# output_stage.net
KiCad netlist of a schematic drawn in EAGLE
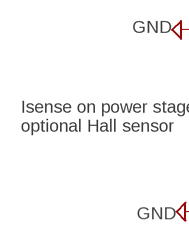
[diagram p0: schematic, sheet 1, part 1 of 2]
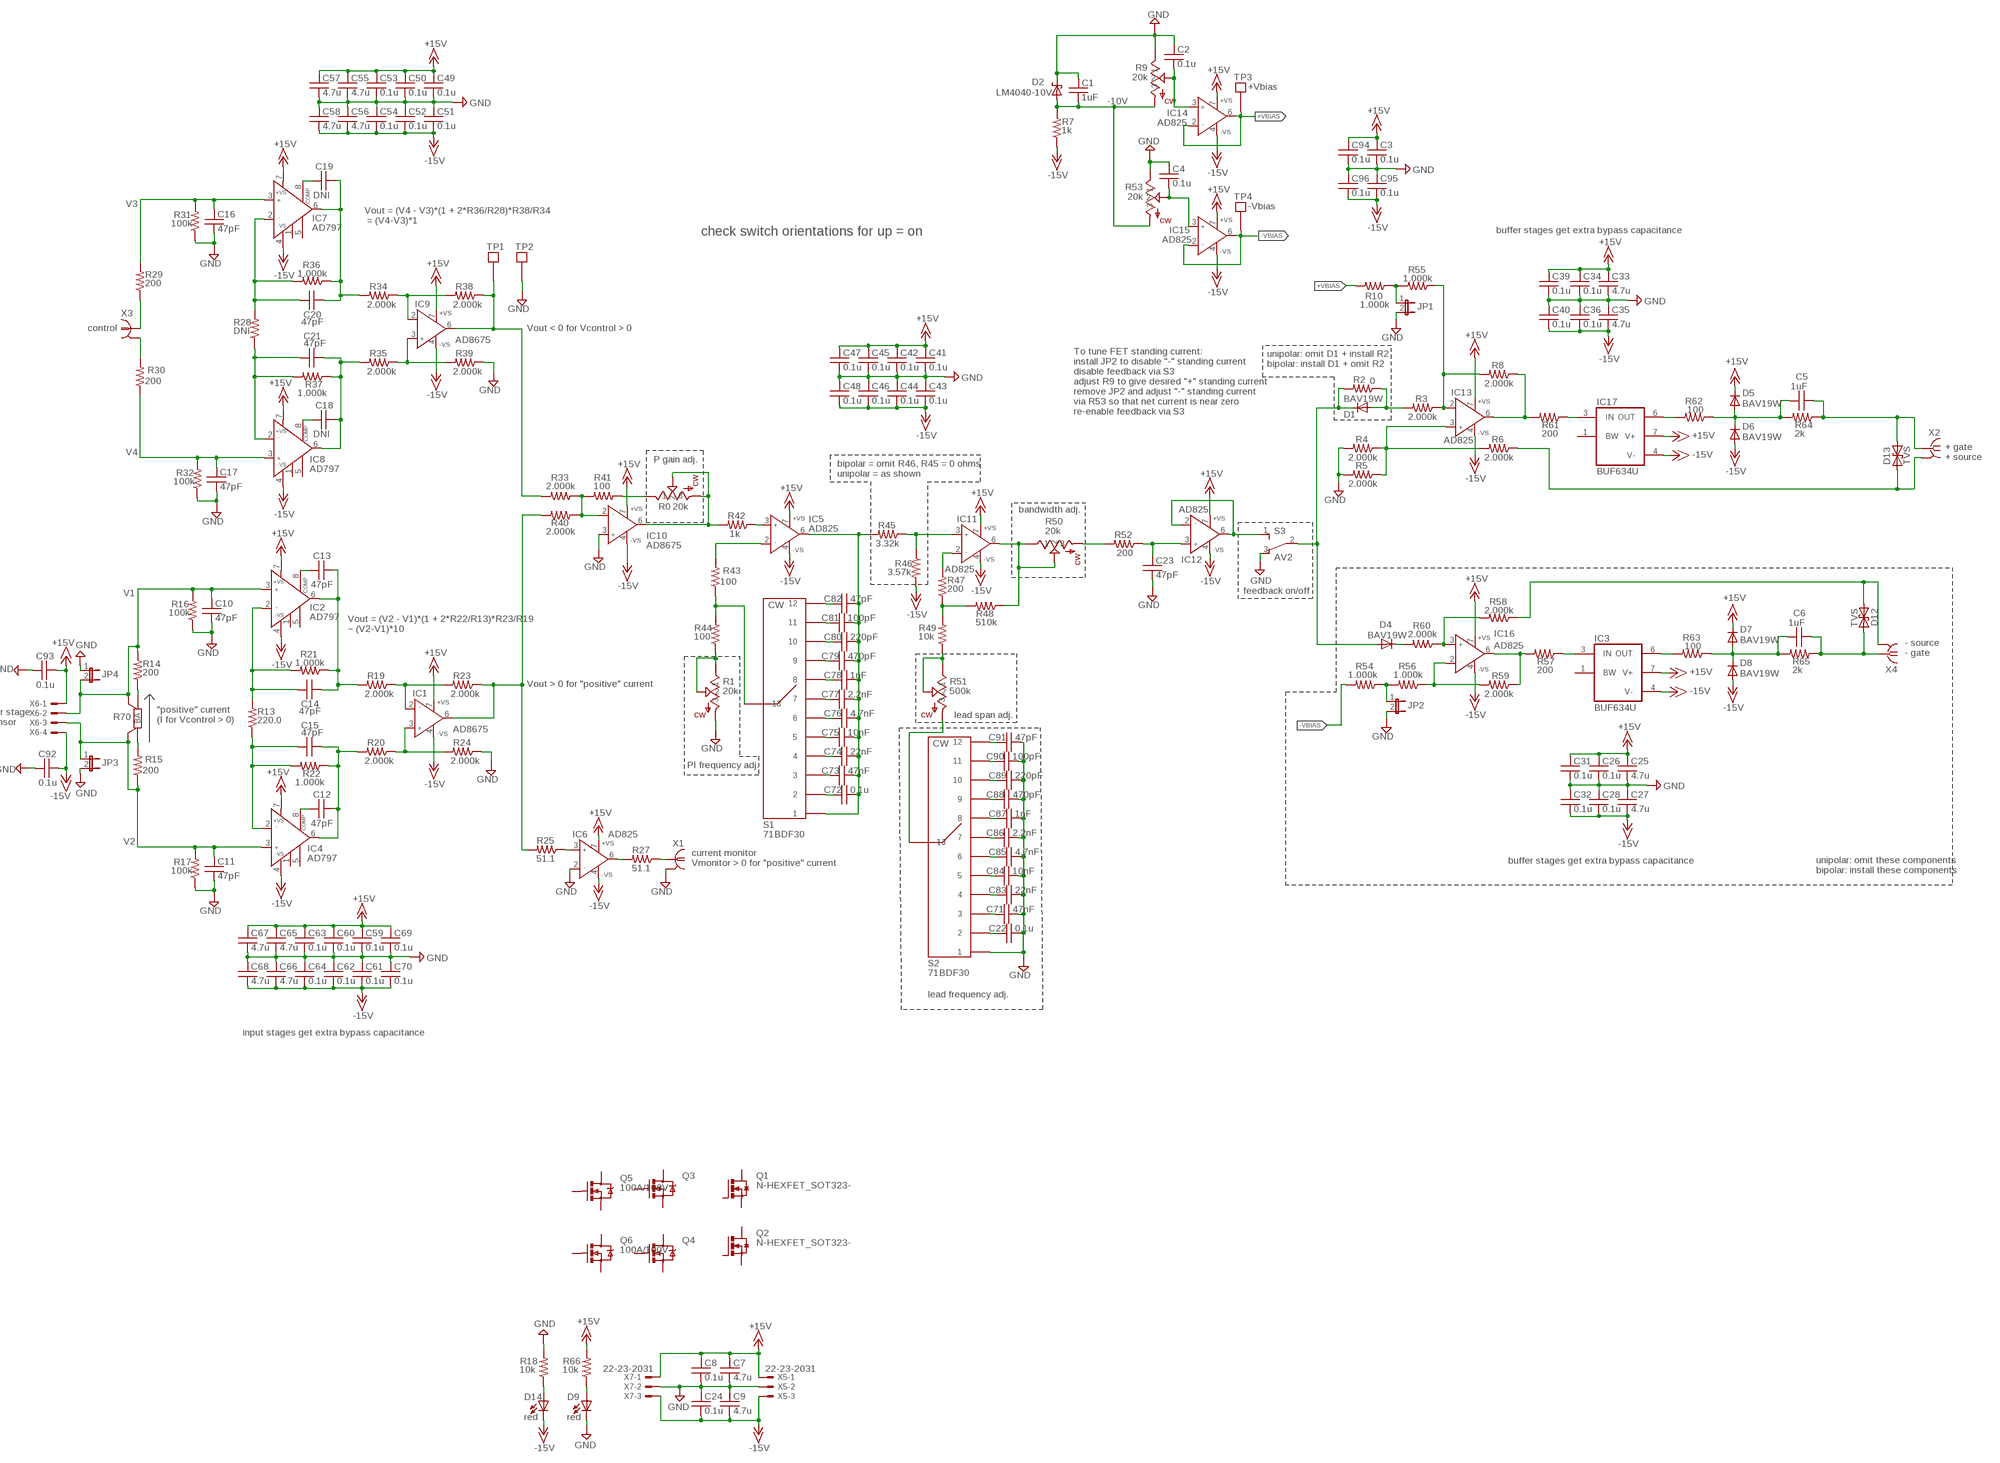
[diagram p1: schematic, sheet 1, part 2 of 2]

(export (version "E")
  (design (tool "Eeschema 10.0.6"))
  (components
    (comp (ref "C1")
      (value "1uF")
      (footprint "eagle-import:0603")
      (libsource (lib "eagle-import") (part "C0603"))
    )
    (comp (ref "C2")
      (value "0.1u")
      (footprint "eagle-import:0603")
      (libsource (lib "eagle-import") (part "C0603"))
    )
    (comp (ref "C3")
      (value "0.1u")
      (footprint "eagle-import:0603")
      (libsource (lib "eagle-import") (part "C0603"))
    )
    (comp (ref "C4")
      (value "0.1u")
      (footprint "eagle-import:0603")
      (libsource (lib "eagle-import") (part "C0603"))
    )
    (comp (ref "C5")
      (value "1uF")
      (footprint "eagle-import:0603")
      (libsource (lib "eagle-import") (part "C0603"))
    )
    (comp (ref "C6")
      (value "1uF")
      (footprint "eagle-import:0603")
      (libsource (lib "eagle-import") (part "C0603"))
    )
    (comp (ref "C7")
      (value "4.7u")
      (footprint "eagle-import:0603")
      (libsource (lib "eagle-import") (part "C0603"))
    )
    (comp (ref "C8")
      (value "0.1u")
      (footprint "eagle-import:0603")
      (libsource (lib "eagle-import") (part "C0603"))
    )
    (comp (ref "C9")
      (value "4.7u")
      (footprint "eagle-import:0603")
      (libsource (lib "eagle-import") (part "C0603"))
    )
    (comp (ref "C10")
      (value "47pF")
      (footprint "eagle-import:0603")
      (libsource (lib "eagle-import") (part "C0603"))
    )
    (comp (ref "C11")
      (value "47pF")
      (footprint "eagle-import:0603")
      (libsource (lib "eagle-import") (part "C0603"))
    )
    (comp (ref "C12")
      (value "47pF")
      (footprint "eagle-import:0603")
      (libsource (lib "eagle-import") (part "C0603"))
    )
    (comp (ref "C13")
      (value "47pF")
      (footprint "eagle-import:0603")
      (libsource (lib "eagle-import") (part "C0603"))
    )
    (comp (ref "C14")
      (value "47pF")
      (footprint "eagle-import:0603")
      (libsource (lib "eagle-import") (part "C0603"))
    )
    (comp (ref "C15")
      (value "47pF")
      (footprint "eagle-import:0603")
      (libsource (lib "eagle-import") (part "C0603"))
    )
    (comp (ref "C16")
      (value "47pF")
      (footprint "eagle-import:0603")
      (libsource (lib "eagle-import") (part "C0603"))
    )
    (comp (ref "C17")
      (value "47pF")
      (footprint "eagle-import:0603")
      (libsource (lib "eagle-import") (part "C0603"))
    )
    (comp (ref "C18")
      (value "DNI")
      (footprint "eagle-import:0603")
      (libsource (lib "eagle-import") (part "C0603"))
    )
    (comp (ref "C19")
      (value "DNI")
      (footprint "eagle-import:0603")
      (libsource (lib "eagle-import") (part "C0603"))
    )
    (comp (ref "C20")
      (value "47pF")
      (footprint "eagle-import:0603")
      (libsource (lib "eagle-import") (part "C0603"))
    )
    (comp (ref "C21")
      (value "47pF")
      (footprint "eagle-import:0603")
      (libsource (lib "eagle-import") (part "C0603"))
    )
    (comp (ref "C22")
      (value "0.1u")
      (footprint "eagle-import:0603")
      (libsource (lib "eagle-import") (part "C0603"))
    )
    (comp (ref "C23")
      (value "47pF")
      (footprint "eagle-import:0603")
      (libsource (lib "eagle-import") (part "C0603"))
    )
    (comp (ref "C24")
      (value "0.1u")
      (footprint "eagle-import:0603")
      (libsource (lib "eagle-import") (part "C0603"))
    )
    (comp (ref "C25")
      (value "4.7u")
      (footprint "eagle-import:0603")
      (libsource (lib "eagle-import") (part "C0603"))
    )
    (comp (ref "C26")
      (value "0.1u")
      (footprint "eagle-import:0603")
      (libsource (lib "eagle-import") (part "C0603"))
    )
    (comp (ref "C27")
      (value "4.7u")
      (footprint "eagle-import:0603")
      (libsource (lib "eagle-import") (part "C0603"))
    )
    (comp (ref "C28")
      (value "0.1u")
      (footprint "eagle-import:0603")
      (libsource (lib "eagle-import") (part "C0603"))
    )
    (comp (ref "C31")
      (value "0.1u")
      (footprint "eagle-import:0603")
      (libsource (lib "eagle-import") (part "C0603"))
    )
    (comp (ref "C32")
      (value "0.1u")
      (footprint "eagle-import:0603")
      (libsource (lib "eagle-import") (part "C0603"))
    )
    (comp (ref "C33")
      (value "4.7u")
      (footprint "eagle-import:0603")
      (libsource (lib "eagle-import") (part "C0603"))
    )
    (comp (ref "C34")
      (value "0.1u")
      (footprint "eagle-import:0603")
      (libsource (lib "eagle-import") (part "C0603"))
    )
    (comp (ref "C35")
      (value "4.7u")
      (footprint "eagle-import:0603")
      (libsource (lib "eagle-import") (part "C0603"))
    )
    (comp (ref "C36")
      (value "0.1u")
      (footprint "eagle-import:0603")
      (libsource (lib "eagle-import") (part "C0603"))
    )
    (comp (ref "C39")
      (value "0.1u")
      (footprint "eagle-import:0603")
      (libsource (lib "eagle-import") (part "C0603"))
    )
    (comp (ref "C40")
      (value "0.1u")
      (footprint "eagle-import:0603")
      (libsource (lib "eagle-import") (part "C0603"))
    )
    (comp (ref "C41")
      (value "0.1u")
      (footprint "eagle-import:0603")
      (libsource (lib "eagle-import") (part "C0603"))
    )
    (comp (ref "C42")
      (value "0.1u")
      (footprint "eagle-import:0603")
      (libsource (lib "eagle-import") (part "C0603"))
    )
    (comp (ref "C43")
      (value "0.1u")
      (footprint "eagle-import:0603")
      (libsource (lib "eagle-import") (part "C0603"))
    )
    (comp (ref "C44")
      (value "0.1u")
      (footprint "eagle-import:0603")
      (libsource (lib "eagle-import") (part "C0603"))
    )
    (comp (ref "C45")
      (value "0.1u")
      (footprint "eagle-import:0603")
      (libsource (lib "eagle-import") (part "C0603"))
    )
    (comp (ref "C46")
      (value "0.1u")
      (footprint "eagle-import:0603")
      (libsource (lib "eagle-import") (part "C0603"))
    )
    (comp (ref "C47")
      (value "0.1u")
      (footprint "eagle-import:0603")
      (libsource (lib "eagle-import") (part "C0603"))
    )
    (comp (ref "C48")
      (value "0.1u")
      (footprint "eagle-import:0603")
      (libsource (lib "eagle-import") (part "C0603"))
    )
    (comp (ref "C49")
      (value "0.1u")
      (footprint "eagle-import:0603")
      (libsource (lib "eagle-import") (part "C0603"))
    )
    (comp (ref "C50")
      (value "0.1u")
      (footprint "eagle-import:0603")
      (libsource (lib "eagle-import") (part "C0603"))
    )
    (comp (ref "C51")
      (value "0.1u")
      (footprint "eagle-import:0603")
      (libsource (lib "eagle-import") (part "C0603"))
    )
    (comp (ref "C52")
      (value "0.1u")
      (footprint "eagle-import:0603")
      (libsource (lib "eagle-import") (part "C0603"))
    )
    (comp (ref "C53")
      (value "0.1u")
      (footprint "eagle-import:0603")
      (libsource (lib "eagle-import") (part "C0603"))
    )
    (comp (ref "C54")
      (value "0.1u")
      (footprint "eagle-import:0603")
      (libsource (lib "eagle-import") (part "C0603"))
    )
    (comp (ref "C55")
      (value "4.7u")
      (footprint "eagle-import:0603")
      (libsource (lib "eagle-import") (part "C0603"))
    )
    (comp (ref "C56")
      (value "4.7u")
      (footprint "eagle-import:0603")
      (libsource (lib "eagle-import") (part "C0603"))
    )
    (comp (ref "C57")
      (value "4.7u")
      (footprint "eagle-import:0603")
      (libsource (lib "eagle-import") (part "C0603"))
    )
    (comp (ref "C58")
      (value "4.7u")
      (footprint "eagle-import:0603")
      (libsource (lib "eagle-import") (part "C0603"))
    )
    (comp (ref "C59")
      (value "0.1u")
      (footprint "eagle-import:0603")
      (libsource (lib "eagle-import") (part "C0603"))
    )
    (comp (ref "C60")
      (value "0.1u")
      (footprint "eagle-import:0603")
      (libsource (lib "eagle-import") (part "C0603"))
    )
    (comp (ref "C61")
      (value "0.1u")
      (footprint "eagle-import:0603")
      (libsource (lib "eagle-import") (part "C0603"))
    )
    (comp (ref "C62")
      (value "0.1u")
      (footprint "eagle-import:0603")
      (libsource (lib "eagle-import") (part "C0603"))
    )
    (comp (ref "C63")
      (value "0.1u")
      (footprint "eagle-import:0603")
      (libsource (lib "eagle-import") (part "C0603"))
    )
    (comp (ref "C64")
      (value "0.1u")
      (footprint "eagle-import:0603")
      (libsource (lib "eagle-import") (part "C0603"))
    )
    (comp (ref "C65")
      (value "4.7u")
      (footprint "eagle-import:0603")
      (libsource (lib "eagle-import") (part "C0603"))
    )
    (comp (ref "C66")
      (value "4.7u")
      (footprint "eagle-import:0603")
      (libsource (lib "eagle-import") (part "C0603"))
    )
    (comp (ref "C67")
      (value "4.7u")
      (footprint "eagle-import:0603")
      (libsource (lib "eagle-import") (part "C0603"))
    )
    (comp (ref "C68")
      (value "4.7u")
      (footprint "eagle-import:0603")
      (libsource (lib "eagle-import") (part "C0603"))
    )
    (comp (ref "C69")
      (value "0.1u")
      (footprint "eagle-import:0603")
      (libsource (lib "eagle-import") (part "C0603"))
    )
    (comp (ref "C70")
      (value "0.1u")
      (footprint "eagle-import:0603")
      (libsource (lib "eagle-import") (part "C0603"))
    )
    (comp (ref "C71")
      (value "47nF")
      (footprint "eagle-import:0603")
      (libsource (lib "eagle-import") (part "C0603"))
    )
    (comp (ref "C72")
      (value "0.1u")
      (footprint "eagle-import:0603")
      (libsource (lib "eagle-import") (part "C0603"))
    )
    (comp (ref "C73")
      (value "47nF")
      (footprint "eagle-import:0603")
      (libsource (lib "eagle-import") (part "C0603"))
    )
    (comp (ref "C74")
      (value "22nF")
      (footprint "eagle-import:0603")
      (libsource (lib "eagle-import") (part "C0603"))
    )
    (comp (ref "C75")
      (value "10nF")
      (footprint "eagle-import:0603")
      (libsource (lib "eagle-import") (part "C0603"))
    )
    (comp (ref "C76")
      (value "4.7nF")
      (footprint "eagle-import:0603")
      (libsource (lib "eagle-import") (part "C0603"))
    )
    (comp (ref "C77")
      (value "2.2nF")
      (footprint "eagle-import:0603")
      (libsource (lib "eagle-import") (part "C0603"))
    )
    (comp (ref "C78")
      (value "1nF")
      (footprint "eagle-import:0603")
      (libsource (lib "eagle-import") (part "C0603"))
    )
    (comp (ref "C79")
      (value "470pF")
      (footprint "eagle-import:0603")
      (libsource (lib "eagle-import") (part "C0603"))
    )
    (comp (ref "C80")
      (value "220pF")
      (footprint "eagle-import:0603")
      (libsource (lib "eagle-import") (part "C0603"))
    )
    (comp (ref "C81")
      (value "100pF")
      (footprint "eagle-import:0603")
      (libsource (lib "eagle-import") (part "C0603"))
    )
    (comp (ref "C82")
      (value "47pF")
      (footprint "eagle-import:0603")
      (libsource (lib "eagle-import") (part "C0603"))
    )
    (comp (ref "C83")
      (value "22nF")
      (footprint "eagle-import:0603")
      (libsource (lib "eagle-import") (part "C0603"))
    )
    (comp (ref "C84")
      (value "10nF")
      (footprint "eagle-import:0603")
      (libsource (lib "eagle-import") (part "C0603"))
    )
    (comp (ref "C85")
      (value "4.7nF")
      (footprint "eagle-import:0603")
      (libsource (lib "eagle-import") (part "C0603"))
    )
    (comp (ref "C86")
      (value "2.2nF")
      (footprint "eagle-import:0603")
      (libsource (lib "eagle-import") (part "C0603"))
    )
    (comp (ref "C87")
      (value "1nF")
      (footprint "eagle-import:0603")
      (libsource (lib "eagle-import") (part "C0603"))
    )
    (comp (ref "C88")
      (value "470pF")
      (footprint "eagle-import:0603")
      (libsource (lib "eagle-import") (part "C0603"))
    )
    (comp (ref "C89")
      (value "220pF")
      (footprint "eagle-import:0603")
      (libsource (lib "eagle-import") (part "C0603"))
    )
    (comp (ref "C90")
      (value "100pF")
      (footprint "eagle-import:0603")
      (libsource (lib "eagle-import") (part "C0603"))
    )
    (comp (ref "C91")
      (value "47pF")
      (footprint "eagle-import:0603")
      (libsource (lib "eagle-import") (part "C0603"))
    )
    (comp (ref "C92")
      (value "0.1u")
      (footprint "eagle-import:0603")
      (libsource (lib "eagle-import") (part "C0603"))
    )
    (comp (ref "C93")
      (value "0.1u")
      (footprint "eagle-import:0603")
      (libsource (lib "eagle-import") (part "C0603"))
    )
    (comp (ref "C94")
      (value "0.1u")
      (footprint "eagle-import:0603")
      (libsource (lib "eagle-import") (part "C0603"))
    )
    (comp (ref "C95")
      (value "0.1u")
      (footprint "eagle-import:0603")
      (libsource (lib "eagle-import") (part "C0603"))
    )
    (comp (ref "C96")
      (value "0.1u")
      (footprint "eagle-import:0603")
      (libsource (lib "eagle-import") (part "C0603"))
    )
    (comp (ref "D1")
      (value "BAV19W")
      (footprint "eagle-import:SOD123")
      (libsource (lib "eagle-import") (part "DIODE-SOD123"))
    )
    (comp (ref "D2")
      (value "LM4040-10V")
      (footprint "eagle-import:SOT23")
      (libsource (lib "eagle-import") (part "LM4040"))
    )
    (comp (ref "D4")
      (value "BAV19W")
      (footprint "eagle-import:SOD123")
      (libsource (lib "eagle-import") (part "DIODE-SOD123"))
    )
    (comp (ref "D5")
      (value "BAV19W")
      (footprint "eagle-import:SOD123")
      (libsource (lib "eagle-import") (part "DIODE-SOD123"))
    )
    (comp (ref "D6")
      (value "BAV19W")
      (footprint "eagle-import:SOD123")
      (libsource (lib "eagle-import") (part "DIODE-SOD123"))
    )
    (comp (ref "D7")
      (value "BAV19W")
      (footprint "eagle-import:SOD123")
      (libsource (lib "eagle-import") (part "DIODE-SOD123"))
    )
    (comp (ref "D8")
      (value "BAV19W")
      (footprint "eagle-import:SOD123")
      (libsource (lib "eagle-import") (part "DIODE-SOD123"))
    )
    (comp (ref "D9")
      (value "red")
      (footprint "eagle-import:LED0603")
      (libsource (lib "eagle-import") (part "LED0603"))
    )
    (comp (ref "D12")
      (value "TVS")
      (footprint "eagle-import:SMA-DIODE")
      (libsource (lib "eagle-import") (part "TVS"))
    )
    (comp (ref "D13")
      (value "TVS")
      (footprint "eagle-import:SMA-DIODE")
      (libsource (lib "eagle-import") (part "TVS"))
    )
    (comp (ref "D14")
      (value "red")
      (footprint "eagle-import:LED0603")
      (libsource (lib "eagle-import") (part "LED0603"))
    )
    (comp (ref "IC1")
      (value "AD8675")
      (footprint "eagle-import:SO8")
      (fields (field (name "MF") "ALTERA CORPORATION") (field (name "MPN") "AD825ARZ"))
      (libsource (lib "eagle-import") (part "AD825_BR"))
    )
    (comp (ref "IC2")
      (value "AD797")
      (footprint "eagle-import:SO8")
      (fields (field (name "MF") "ALTERA CORPORATION") (field (name "MPN") "AD797ARZ"))
      (libsource (lib "eagle-import") (part "AD797_AR"))
    )
    (comp (ref "IC3")
      (value "BUF634U")
      (footprint "eagle-import:SO08")
      (fields (field (name "MF") "TEXAS INSTRUMENTS"))
      (libsource (lib "eagle-import") (part "BUF634U"))
    )
    (comp (ref "IC4")
      (value "AD797")
      (footprint "eagle-import:SO8")
      (fields (field (name "MF") "ALTERA CORPORATION") (field (name "MPN") "AD797ARZ"))
      (libsource (lib "eagle-import") (part "AD797_BR"))
    )
    (comp (ref "IC5")
      (value "AD825")
      (footprint "eagle-import:SO08")
      (libsource (lib "eagle-import") (part "AD825_A"))
    )
    (comp (ref "IC6")
      (value "AD825")
      (footprint "eagle-import:SO08")
      (libsource (lib "eagle-import") (part "AD825_A"))
    )
    (comp (ref "IC7")
      (value "AD797")
      (footprint "eagle-import:SO8")
      (fields (field (name "MF") "ALTERA CORPORATION") (field (name "MPN") "AD797ARZ"))
      (libsource (lib "eagle-import") (part "AD797_AR"))
    )
    (comp (ref "IC8")
      (value "AD797")
      (footprint "eagle-import:SO8")
      (fields (field (name "MF") "ALTERA CORPORATION") (field (name "MPN") "AD797ARZ"))
      (libsource (lib "eagle-import") (part "AD797_BR"))
    )
    (comp (ref "IC9")
      (value "AD8675")
      (footprint "eagle-import:SO8")
      (fields (field (name "MF") "ALTERA CORPORATION") (field (name "MPN") "AD825ARZ"))
      (libsource (lib "eagle-import") (part "AD825_BR"))
    )
    (comp (ref "IC10")
      (value "AD8675")
      (footprint "eagle-import:SO8")
      (fields (field (name "MF") "ALTERA CORPORATION") (field (name "MPN") "AD825ARZ"))
      (libsource (lib "eagle-import") (part "AD825_BR"))
    )
    (comp (ref "IC11")
      (value "AD825")
      (footprint "eagle-import:SO08")
      (libsource (lib "eagle-import") (part "AD825_A"))
    )
    (comp (ref "IC12")
      (value "AD825")
      (footprint "eagle-import:SO8")
      (fields (field (name "MF") "ALTERA CORPORATION") (field (name "MPN") "AD825ARZ"))
      (libsource (lib "eagle-import") (part "AD825_BR"))
    )
    (comp (ref "IC13")
      (value "AD825")
      (footprint "eagle-import:SO8")
      (fields (field (name "MF") "ALTERA CORPORATION") (field (name "MPN") "AD825ARZ"))
      (libsource (lib "eagle-import") (part "AD825_BR"))
    )
    (comp (ref "IC14")
      (value "AD825")
      (footprint "eagle-import:SO08")
      (libsource (lib "eagle-import") (part "AD825_A"))
    )
    (comp (ref "IC15")
      (value "AD825")
      (footprint "eagle-import:SO08")
      (libsource (lib "eagle-import") (part "AD825_A"))
    )
    (comp (ref "IC16")
      (value "AD825")
      (footprint "eagle-import:SO08")
      (libsource (lib "eagle-import") (part "AD825_A"))
    )
    (comp (ref "IC17")
      (value "BUF634U")
      (footprint "eagle-import:SO08")
      (fields (field (name "MF") "TEXAS INSTRUMENTS"))
      (libsource (lib "eagle-import") (part "BUF634U"))
    )
    (comp (ref "JP1")
      (value "JP1E")
      (footprint "eagle-import:JP1")
      (libsource (lib "eagle-import") (part "JP1E"))
    )
    (comp (ref "JP2")
      (value "JP1E")
      (footprint "eagle-import:JP1")
      (libsource (lib "eagle-import") (part "JP1E"))
    )
    (comp (ref "JP3")
      (value "JP1E")
      (footprint "eagle-import:JP1")
      (libsource (lib "eagle-import") (part "JP1E"))
    )
    (comp (ref "JP4")
      (value "JP1E")
      (footprint "eagle-import:JP1")
      (libsource (lib "eagle-import") (part "JP1E"))
    )
    (comp (ref "Q1")
      (value "N-HEXFET_SOT323-")
      (footprint "eagle-import:SOT223")
      (libsource (lib "eagle-import") (part "N-HEXFET_?-SOT323"))
    )
    (comp (ref "Q2")
      (value "N-HEXFET_SOT323-")
      (footprint "eagle-import:SOT223")
      (libsource (lib "eagle-import") (part "N-HEXFET_?-SOT323"))
    )
    (comp (ref "Q3")
      (value "MOSFET-NCHANNELFDD8780")
      (footprint "eagle-import:DPAK")
      (libsource (lib "eagle-import") (part "MOSFET-NCHANNELFDD8780"))
    )
    (comp (ref "Q4")
      (value "MOSFET-NCHANNELFDD8780")
      (footprint "eagle-import:DPAK")
      (libsource (lib "eagle-import") (part "MOSFET-NCHANNELFDD8780"))
    )
    (comp (ref "Q5")
      (value "100A/100V")
      (footprint "eagle-import:TO-263_D2PAK")
      (libsource (lib "eagle-import") (part "MOSFET-NCHANNELPSMN7R0"))
    )
    (comp (ref "Q6")
      (value "100A/100V")
      (footprint "eagle-import:TO-263_D2PAK")
      (libsource (lib "eagle-import") (part "MOSFET-NCHANNELPSMN7R0"))
    )
    (comp (ref "R0")
      (value "20k")
      (footprint "eagle-import:3590")
      (libsource (lib "eagle-import") (part "POT"))
    )
    (comp (ref "R1")
      (value "20k")
      (footprint "eagle-import:SP19L")
      (libsource (lib "eagle-import") (part "TRIM_US-B90P"))
    )
    (comp (ref "R2")
      (value "0")
      (footprint "eagle-import:0603")
      (libsource (lib "eagle-import") (part "R0603"))
    )
    (comp (ref "R3")
      (value "2.000k")
      (footprint "eagle-import:0603")
      (libsource (lib "eagle-import") (part "R0603"))
    )
    (comp (ref "R4")
      (value "2.000k")
      (footprint "eagle-import:0603")
      (libsource (lib "eagle-import") (part "R0603"))
    )
    (comp (ref "R5")
      (value "2.000k")
      (footprint "eagle-import:0603")
      (libsource (lib "eagle-import") (part "R0603"))
    )
    (comp (ref "R6")
      (value "2.000k")
      (footprint "eagle-import:0603")
      (libsource (lib "eagle-import") (part "R0603"))
    )
    (comp (ref "R7")
      (value "1k")
      (footprint "eagle-import:0603")
      (libsource (lib "eagle-import") (part "R0603"))
    )
    (comp (ref "R8")
      (value "2.000k")
      (footprint "eagle-import:0603")
      (libsource (lib "eagle-import") (part "R0603"))
    )
    (comp (ref "R9")
      (value "20k")
      (footprint "eagle-import:SP19L")
      (libsource (lib "eagle-import") (part "TRIM_US-B90P"))
    )
    (comp (ref "R10")
      (value "1.000k")
      (footprint "eagle-import:0603")
      (libsource (lib "eagle-import") (part "R0603"))
    )
    (comp (ref "R13")
      (value "220.0")
      (footprint "eagle-import:0603")
      (libsource (lib "eagle-import") (part "R0603"))
    )
    (comp (ref "R14")
      (value "200")
      (footprint "eagle-import:0603")
      (libsource (lib "eagle-import") (part "R0603"))
    )
    (comp (ref "R15")
      (value "200")
      (footprint "eagle-import:0603")
      (libsource (lib "eagle-import") (part "R0603"))
    )
    (comp (ref "R16")
      (value "100k")
      (footprint "eagle-import:0603")
      (libsource (lib "eagle-import") (part "R0603"))
    )
    (comp (ref "R17")
      (value "100k")
      (footprint "eagle-import:0603")
      (libsource (lib "eagle-import") (part "R0603"))
    )
    (comp (ref "R18")
      (value "10k")
      (footprint "eagle-import:0603")
      (libsource (lib "eagle-import") (part "R0603"))
    )
    (comp (ref "R19")
      (value "2.000k")
      (footprint "eagle-import:0603")
      (libsource (lib "eagle-import") (part "R0603"))
    )
    (comp (ref "R20")
      (value "2.000k")
      (footprint "eagle-import:0603")
      (libsource (lib "eagle-import") (part "R0603"))
    )
    (comp (ref "R21")
      (value "1.000k")
      (footprint "eagle-import:0603")
      (libsource (lib "eagle-import") (part "R0603"))
    )
    (comp (ref "R22")
      (value "1.000k")
      (footprint "eagle-import:0603")
      (libsource (lib "eagle-import") (part "R0603"))
    )
    (comp (ref "R23")
      (value "2.000k")
      (footprint "eagle-import:0603")
      (libsource (lib "eagle-import") (part "R0603"))
    )
    (comp (ref "R24")
      (value "2.000k")
      (footprint "eagle-import:0603")
      (libsource (lib "eagle-import") (part "R0603"))
    )
    (comp (ref "R25")
      (value "51.1")
      (footprint "eagle-import:0603")
      (libsource (lib "eagle-import") (part "R0603"))
    )
    (comp (ref "R27")
      (value "51.1")
      (footprint "eagle-import:0603")
      (libsource (lib "eagle-import") (part "R0603"))
    )
    (comp (ref "R28")
      (value "DNI")
      (footprint "eagle-import:0603")
      (libsource (lib "eagle-import") (part "R0603"))
    )
    (comp (ref "R29")
      (value "200")
      (footprint "eagle-import:0603")
      (libsource (lib "eagle-import") (part "R0603"))
    )
    (comp (ref "R30")
      (value "200")
      (footprint "eagle-import:0603")
      (libsource (lib "eagle-import") (part "R0603"))
    )
    (comp (ref "R31")
      (value "100k")
      (footprint "eagle-import:0603")
      (libsource (lib "eagle-import") (part "R0603"))
    )
    (comp (ref "R32")
      (value "100k")
      (footprint "eagle-import:0603")
      (libsource (lib "eagle-import") (part "R0603"))
    )
    (comp (ref "R33")
      (value "2.000k")
      (footprint "eagle-import:0603")
      (libsource (lib "eagle-import") (part "R0603"))
    )
    (comp (ref "R34")
      (value "2.000k")
      (footprint "eagle-import:0603")
      (libsource (lib "eagle-import") (part "R0603"))
    )
    (comp (ref "R35")
      (value "2.000k")
      (footprint "eagle-import:0603")
      (libsource (lib "eagle-import") (part "R0603"))
    )
    (comp (ref "R36")
      (value "1.000k")
      (footprint "eagle-import:0603")
      (libsource (lib "eagle-import") (part "R0603"))
    )
    (comp (ref "R37")
      (value "1.000k")
      (footprint "eagle-import:0603")
      (libsource (lib "eagle-import") (part "R0603"))
    )
    (comp (ref "R38")
      (value "2.000k")
      (footprint "eagle-import:0603")
      (libsource (lib "eagle-import") (part "R0603"))
    )
    (comp (ref "R39")
      (value "2.000k")
      (footprint "eagle-import:0603")
      (libsource (lib "eagle-import") (part "R0603"))
    )
    (comp (ref "R40")
      (value "2.000k")
      (footprint "eagle-import:0603")
      (libsource (lib "eagle-import") (part "R0603"))
    )
    (comp (ref "R41")
      (value "100")
      (footprint "eagle-import:0603")
      (libsource (lib "eagle-import") (part "R0603"))
    )
    (comp (ref "R42")
      (value "1k")
      (footprint "eagle-import:0603")
      (libsource (lib "eagle-import") (part "R0603"))
    )
    (comp (ref "R43")
      (value "100")
      (footprint "eagle-import:0603")
      (libsource (lib "eagle-import") (part "R0603"))
    )
    (comp (ref "R44")
      (value "100")
      (footprint "eagle-import:0603")
      (libsource (lib "eagle-import") (part "R0603"))
    )
    (comp (ref "R45")
      (value "3.32k")
      (footprint "eagle-import:0603")
      (libsource (lib "eagle-import") (part "R0603"))
    )
    (comp (ref "R46")
      (value "3.57k")
      (footprint "eagle-import:0603")
      (libsource (lib "eagle-import") (part "R0603"))
    )
    (comp (ref "R47")
      (value "200")
      (footprint "eagle-import:0603")
      (libsource (lib "eagle-import") (part "R0603"))
    )
    (comp (ref "R48")
      (value "510k")
      (footprint "eagle-import:0603")
      (libsource (lib "eagle-import") (part "R0603"))
    )
    (comp (ref "R49")
      (value "10k")
      (footprint "eagle-import:0603")
      (libsource (lib "eagle-import") (part "R0603"))
    )
    (comp (ref "R50")
      (value "20k")
      (footprint "eagle-import:SP19L")
      (libsource (lib "eagle-import") (part "TRIM_US-B90P"))
    )
    (comp (ref "R51")
      (value "500k")
      (footprint "eagle-import:SP19L")
      (libsource (lib "eagle-import") (part "TRIM_US-B90P"))
    )
    (comp (ref "R52")
      (value "200")
      (footprint "eagle-import:0603")
      (libsource (lib "eagle-import") (part "R0603"))
    )
    (comp (ref "R53")
      (value "20k")
      (footprint "eagle-import:SP19L")
      (libsource (lib "eagle-import") (part "TRIM_US-B90P"))
    )
    (comp (ref "R54")
      (value "1.000k")
      (footprint "eagle-import:0603")
      (libsource (lib "eagle-import") (part "R0603"))
    )
    (comp (ref "R55")
      (value "1.000k")
      (footprint "eagle-import:0603")
      (libsource (lib "eagle-import") (part "R0603"))
    )
    (comp (ref "R56")
      (value "1.000k")
      (footprint "eagle-import:0603")
      (libsource (lib "eagle-import") (part "R0603"))
    )
    (comp (ref "R57")
      (value "200")
      (footprint "eagle-import:0603")
      (libsource (lib "eagle-import") (part "R0603"))
    )
    (comp (ref "R58")
      (value "2.000k")
      (footprint "eagle-import:0603")
      (libsource (lib "eagle-import") (part "R0603"))
    )
    (comp (ref "R59")
      (value "2.000k")
      (footprint "eagle-import:0603")
      (libsource (lib "eagle-import") (part "R0603"))
    )
    (comp (ref "R60")
      (value "2.000k")
      (footprint "eagle-import:0603")
      (libsource (lib "eagle-import") (part "R0603"))
    )
    (comp (ref "R61")
      (value "200")
      (footprint "eagle-import:0603")
      (libsource (lib "eagle-import") (part "R0603"))
    )
    (comp (ref "R62")
      (value "100")
      (footprint "eagle-import:0603")
      (libsource (lib "eagle-import") (part "R0603"))
    )
    (comp (ref "R63")
      (value "100")
      (footprint "eagle-import:0603")
      (libsource (lib "eagle-import") (part "R0603"))
    )
    (comp (ref "R64")
      (value "2k")
      (footprint "eagle-import:0603")
      (libsource (lib "eagle-import") (part "R0603"))
    )
    (comp (ref "R65")
      (value "2k")
      (footprint "eagle-import:0603")
      (libsource (lib "eagle-import") (part "R0603"))
    )
    (comp (ref "R66")
      (value "10k")
      (footprint "eagle-import:0603")
      (libsource (lib "eagle-import") (part "R0603"))
    )
    (comp (ref "R70")
      (value "RSENSE")
      (footprint "eagle-import:22-23-2041")
      (libsource (lib "eagle-import") (part "RSENSE"))
    )
    (comp (ref "S1")
      (value "71BDF30")
      (footprint "eagle-import:71BDF")
      (libsource (lib "eagle-import") (part "71BDF30"))
    )
    (comp (ref "S2")
      (value "71BDF30")
      (footprint "eagle-import:71BDF")
      (libsource (lib "eagle-import") (part "71BDF30"))
    )
    (comp (ref "S3")
      (value "AV2")
      (footprint "eagle-import:SPDT-AV2")
      (libsource (lib "eagle-import") (part "SPDT"))
    )
    (comp (ref "TP1")
      (value "TESTPOINT")
      (footprint "eagle-import:TESTPOINT")
      (libsource (lib "eagle-import") (part "TESTPOINT"))
    )
    (comp (ref "TP2")
      (value "TESTPOINT")
      (footprint "eagle-import:TESTPOINT")
      (libsource (lib "eagle-import") (part "TESTPOINT"))
    )
    (comp (ref "TP3")
      (value "TESTPOINT")
      (footprint "eagle-import:TESTPOINT")
      (libsource (lib "eagle-import") (part "TESTPOINT"))
    )
    (comp (ref "TP4")
      (value "TESTPOINT")
      (footprint "eagle-import:TESTPOINT")
      (libsource (lib "eagle-import") (part "TESTPOINT"))
    )
    (comp (ref "X1")
      (value "1-227161-0")
      (footprint "eagle-import:AMP_227161")
      (fields (field (name "MF") "TYCO ELECTRONICS") (field (name "MPN") "1-227161"))
      (libsource (lib "eagle-import") (part "?2271611--0"))
    )
    (comp (ref "X2")
      (value "BU-SMA-H")
      (footprint "eagle-import:BU-SMA-H")
      (libsource (lib "eagle-import") (part "BU-SMA-H"))
    )
    (comp (ref "X3")
      (value "1-227161-0")
      (footprint "eagle-import:AMP_227161")
      (fields (field (name "MF") "TYCO ELECTRONICS") (field (name "MPN") "1-227161"))
      (libsource (lib "eagle-import") (part "?2271611--0"))
    )
    (comp (ref "X4")
      (value "BU-SMA-H")
      (footprint "eagle-import:BU-SMA-H")
      (libsource (lib "eagle-import") (part "BU-SMA-H"))
    )
    (comp (ref "X5")
      (value "22-23-2031")
      (footprint "eagle-import:22-23-2031")
      (fields (field (name "MF") "MOLEX"))
      (libsource (lib "eagle-import") (part "22-23-2031"))
    )
    (comp (ref "X6")
      (value "22-23-2041")
      (footprint "eagle-import:22-23-2041")
      (fields (field (name "MF") "MOLEX"))
      (libsource (lib "eagle-import") (part "22-23-2041"))
    )
    (comp (ref "X7")
      (value "22-23-2031")
      (footprint "eagle-import:22-23-2031")
      (fields (field (name "MF") "MOLEX"))
      (libsource (lib "eagle-import") (part "22-23-2031"))
    )
  )
  (nets
    (net (code "1") (name "+15V") (class "Default")
      (node (ref "C25") (pin "1") (pinfunction "1_1") (pintype "passive"))
      (node (ref "C26") (pin "1") (pinfunction "1_1") (pintype "passive"))
      (node (ref "C3") (pin "1") (pinfunction "1_1") (pintype "passive"))
      (node (ref "C31") (pin "1") (pinfunction "1_1") (pintype "passive"))
      (node (ref "C33") (pin "1") (pinfunction "1_1") (pintype "passive"))
      (node (ref "C34") (pin "1") (pinfunction "1_1") (pintype "passive"))
      (node (ref "C39") (pin "1") (pinfunction "1_1") (pintype "passive"))
      (node (ref "C41") (pin "1") (pinfunction "1_1") (pintype "passive"))
      (node (ref "C42") (pin "1") (pinfunction "1_1") (pintype "passive"))
      (node (ref "C45") (pin "1") (pinfunction "1_1") (pintype "passive"))
      (node (ref "C47") (pin "1") (pinfunction "1_1") (pintype "passive"))
      (node (ref "C49") (pin "1") (pinfunction "1_1") (pintype "passive"))
      (node (ref "C50") (pin "1") (pinfunction "1_1") (pintype "passive"))
      (node (ref "C53") (pin "1") (pinfunction "1_1") (pintype "passive"))
      (node (ref "C55") (pin "1") (pinfunction "1_1") (pintype "passive"))
      (node (ref "C57") (pin "1") (pinfunction "1_1") (pintype "passive"))
      (node (ref "C59") (pin "1") (pinfunction "1_1") (pintype "passive"))
      (node (ref "C60") (pin "1") (pinfunction "1_1") (pintype "passive"))
      (node (ref "C63") (pin "1") (pinfunction "1_1") (pintype "passive"))
      (node (ref "C65") (pin "1") (pinfunction "1_1") (pintype "passive"))
      (node (ref "C67") (pin "1") (pinfunction "1_1") (pintype "passive"))
      (node (ref "C69") (pin "1") (pinfunction "1_1") (pintype "passive"))
      (node (ref "C7") (pin "1") (pinfunction "1_1") (pintype "passive"))
      (node (ref "C8") (pin "1") (pinfunction "1_1") (pintype "passive"))
      (node (ref "C93") (pin "2") (pinfunction "2_2") (pintype "passive"))
      (node (ref "C94") (pin "1") (pinfunction "1_1") (pintype "passive"))
      (node (ref "D5") (pin "C") (pinfunction "C_C") (pintype "passive"))
      (node (ref "D7") (pin "C") (pinfunction "C_C") (pintype "passive"))
      (node (ref "IC1") (pin "7") (pinfunction "+VS_7") (pintype "input"))
      (node (ref "IC10") (pin "7") (pinfunction "+VS_7") (pintype "input"))
      (node (ref "IC11") (pin "7") (pinfunction "+VS_7") (pintype "input"))
      (node (ref "IC12") (pin "7") (pinfunction "+VS_7") (pintype "input"))
      (node (ref "IC13") (pin "7") (pinfunction "+VS_7") (pintype "input"))
      (node (ref "IC14") (pin "7") (pinfunction "+VS_7") (pintype "input"))
      (node (ref "IC15") (pin "7") (pinfunction "+VS_7") (pintype "input"))
      (node (ref "IC16") (pin "7") (pinfunction "+VS_7") (pintype "input"))
      (node (ref "IC17") (pin "7") (pinfunction "V+_7") (pintype "power_in"))
      (node (ref "IC2") (pin "7") (pinfunction "+VS_7") (pintype "input"))
      (node (ref "IC3") (pin "7") (pinfunction "V+_7") (pintype "power_in"))
      (node (ref "IC4") (pin "7") (pinfunction "+VS_7") (pintype "input"))
      (node (ref "IC5") (pin "7") (pinfunction "+VS_7") (pintype "input"))
      (node (ref "IC6") (pin "7") (pinfunction "+VS_7") (pintype "input"))
      (node (ref "IC7") (pin "7") (pinfunction "+VS_7") (pintype "input"))
      (node (ref "IC8") (pin "7") (pinfunction "+VS_7") (pintype "input"))
      (node (ref "IC9") (pin "7") (pinfunction "+VS_7") (pintype "input"))
      (node (ref "R66") (pin "2") (pinfunction "2_2") (pintype "passive"))
      (node (ref "X5") (pin "1") (pinfunction "S_1") (pintype "passive"))
      (node (ref "X6") (pin "1") (pinfunction "S_1") (pintype "passive"))
      (node (ref "X7") (pin "1") (pinfunction "S_1") (pintype "passive"))
    )
    (net (code "2") (name "+VBIAS") (class "Default")
      (node (ref "IC14") (pin "2") (pinfunction "IN-_2") (pintype "input"))
      (node (ref "IC14") (pin "6") (pinfunction "OUT_6") (pintype "output"))
      (node (ref "R10") (pin "2") (pinfunction "2_2") (pintype "passive"))
      (node (ref "TP3") (pin "P$1") (pinfunction "P$1_P$1") (pintype "bidirectional"))
    )
    (net (code "3") (name "-15V") (class "Default")
      (node (ref "C24") (pin "2") (pinfunction "2_2") (pintype "passive"))
      (node (ref "C27") (pin "2") (pinfunction "2_2") (pintype "passive"))
      (node (ref "C28") (pin "2") (pinfunction "2_2") (pintype "passive"))
      (node (ref "C32") (pin "2") (pinfunction "2_2") (pintype "passive"))
      (node (ref "C35") (pin "2") (pinfunction "2_2") (pintype "passive"))
      (node (ref "C36") (pin "2") (pinfunction "2_2") (pintype "passive"))
      (node (ref "C40") (pin "2") (pinfunction "2_2") (pintype "passive"))
      (node (ref "C43") (pin "2") (pinfunction "2_2") (pintype "passive"))
      (node (ref "C44") (pin "2") (pinfunction "2_2") (pintype "passive"))
      (node (ref "C46") (pin "2") (pinfunction "2_2") (pintype "passive"))
      (node (ref "C48") (pin "2") (pinfunction "2_2") (pintype "passive"))
      (node (ref "C51") (pin "2") (pinfunction "2_2") (pintype "passive"))
      (node (ref "C52") (pin "2") (pinfunction "2_2") (pintype "passive"))
      (node (ref "C54") (pin "2") (pinfunction "2_2") (pintype "passive"))
      (node (ref "C56") (pin "2") (pinfunction "2_2") (pintype "passive"))
      (node (ref "C58") (pin "2") (pinfunction "2_2") (pintype "passive"))
      (node (ref "C61") (pin "2") (pinfunction "2_2") (pintype "passive"))
      (node (ref "C62") (pin "2") (pinfunction "2_2") (pintype "passive"))
      (node (ref "C64") (pin "2") (pinfunction "2_2") (pintype "passive"))
      (node (ref "C66") (pin "2") (pinfunction "2_2") (pintype "passive"))
      (node (ref "C68") (pin "2") (pinfunction "2_2") (pintype "passive"))
      (node (ref "C70") (pin "2") (pinfunction "2_2") (pintype "passive"))
      (node (ref "C9") (pin "2") (pinfunction "2_2") (pintype "passive"))
      (node (ref "C92") (pin "2") (pinfunction "2_2") (pintype "passive"))
      (node (ref "C95") (pin "2") (pinfunction "2_2") (pintype "passive"))
      (node (ref "C96") (pin "2") (pinfunction "2_2") (pintype "passive"))
      (node (ref "D14") (pin "C") (pinfunction "C_C") (pintype "passive"))
      (node (ref "D6") (pin "A") (pinfunction "A_A") (pintype "passive"))
      (node (ref "D8") (pin "A") (pinfunction "A_A") (pintype "passive"))
      (node (ref "IC1") (pin "4") (pinfunction "-VS_4") (pintype "input"))
      (node (ref "IC10") (pin "4") (pinfunction "-VS_4") (pintype "input"))
      (node (ref "IC11") (pin "4") (pinfunction "-VS_4") (pintype "input"))
      (node (ref "IC12") (pin "4") (pinfunction "-VS_4") (pintype "input"))
      (node (ref "IC13") (pin "4") (pinfunction "-VS_4") (pintype "input"))
      (node (ref "IC14") (pin "4") (pinfunction "-VS_4") (pintype "input"))
      (node (ref "IC15") (pin "4") (pinfunction "-VS_4") (pintype "input"))
      (node (ref "IC16") (pin "4") (pinfunction "-VS_4") (pintype "input"))
      (node (ref "IC17") (pin "4") (pinfunction "V-_4") (pintype "power_in"))
      (node (ref "IC2") (pin "4") (pinfunction "-VS_4") (pintype "input"))
      (node (ref "IC3") (pin "4") (pinfunction "V-_4") (pintype "power_in"))
      (node (ref "IC4") (pin "4") (pinfunction "-VS_4") (pintype "input"))
      (node (ref "IC5") (pin "4") (pinfunction "-VS_4") (pintype "input"))
      (node (ref "IC6") (pin "4") (pinfunction "-VS_4") (pintype "input"))
      (node (ref "IC7") (pin "4") (pinfunction "-VS_4") (pintype "input"))
      (node (ref "IC8") (pin "4") (pinfunction "-VS_4") (pintype "input"))
      (node (ref "IC9") (pin "4") (pinfunction "-VS_4") (pintype "input"))
      (node (ref "R46") (pin "2") (pinfunction "2_2") (pintype "passive"))
      (node (ref "R7") (pin "1") (pinfunction "1_1") (pintype "passive"))
      (node (ref "X5") (pin "3") (pinfunction "S_3") (pintype "passive"))
      (node (ref "X6") (pin "4") (pinfunction "S_4") (pintype "passive"))
      (node (ref "X7") (pin "3") (pinfunction "S_3") (pintype "passive"))
    )
    (net (code "4") (name "-VBIAS") (class "Default")
      (node (ref "IC15") (pin "2") (pinfunction "IN-_2") (pintype "input"))
      (node (ref "IC15") (pin "6") (pinfunction "OUT_6") (pintype "output"))
      (node (ref "R54") (pin "2") (pinfunction "2_2") (pintype "passive"))
      (node (ref "TP4") (pin "P$1") (pinfunction "P$1_P$1") (pintype "bidirectional"))
    )
    (net (code "5") (name "GND") (class "Default")
      (node (ref "C1") (pin "1") (pinfunction "1_1") (pintype "passive"))
      (node (ref "C10") (pin "2") (pinfunction "2_2") (pintype "passive"))
      (node (ref "C11") (pin "2") (pinfunction "2_2") (pintype "passive"))
      (node (ref "C16") (pin "2") (pinfunction "2_2") (pintype "passive"))
      (node (ref "C17") (pin "2") (pinfunction "2_2") (pintype "passive"))
      (node (ref "C2") (pin "1") (pinfunction "1_1") (pintype "passive"))
      (node (ref "C22") (pin "2") (pinfunction "2_2") (pintype "passive"))
      (node (ref "C23") (pin "2") (pinfunction "2_2") (pintype "passive"))
      (node (ref "C24") (pin "1") (pinfunction "1_1") (pintype "passive"))
      (node (ref "C25") (pin "2") (pinfunction "2_2") (pintype "passive"))
      (node (ref "C26") (pin "2") (pinfunction "2_2") (pintype "passive"))
      (node (ref "C27") (pin "1") (pinfunction "1_1") (pintype "passive"))
      (node (ref "C28") (pin "1") (pinfunction "1_1") (pintype "passive"))
      (node (ref "C3") (pin "2") (pinfunction "2_2") (pintype "passive"))
      (node (ref "C31") (pin "2") (pinfunction "2_2") (pintype "passive"))
      (node (ref "C32") (pin "1") (pinfunction "1_1") (pintype "passive"))
      (node (ref "C33") (pin "2") (pinfunction "2_2") (pintype "passive"))
      (node (ref "C34") (pin "2") (pinfunction "2_2") (pintype "passive"))
      (node (ref "C35") (pin "1") (pinfunction "1_1") (pintype "passive"))
      (node (ref "C36") (pin "1") (pinfunction "1_1") (pintype "passive"))
      (node (ref "C39") (pin "2") (pinfunction "2_2") (pintype "passive"))
      (node (ref "C4") (pin "1") (pinfunction "1_1") (pintype "passive"))
      (node (ref "C40") (pin "1") (pinfunction "1_1") (pintype "passive"))
      (node (ref "C41") (pin "2") (pinfunction "2_2") (pintype "passive"))
      (node (ref "C42") (pin "2") (pinfunction "2_2") (pintype "passive"))
      (node (ref "C43") (pin "1") (pinfunction "1_1") (pintype "passive"))
      (node (ref "C44") (pin "1") (pinfunction "1_1") (pintype "passive"))
      (node (ref "C45") (pin "2") (pinfunction "2_2") (pintype "passive"))
      (node (ref "C46") (pin "1") (pinfunction "1_1") (pintype "passive"))
      (node (ref "C47") (pin "2") (pinfunction "2_2") (pintype "passive"))
      (node (ref "C48") (pin "1") (pinfunction "1_1") (pintype "passive"))
      (node (ref "C49") (pin "2") (pinfunction "2_2") (pintype "passive"))
      (node (ref "C50") (pin "2") (pinfunction "2_2") (pintype "passive"))
      (node (ref "C51") (pin "1") (pinfunction "1_1") (pintype "passive"))
      (node (ref "C52") (pin "1") (pinfunction "1_1") (pintype "passive"))
      (node (ref "C53") (pin "2") (pinfunction "2_2") (pintype "passive"))
      (node (ref "C54") (pin "1") (pinfunction "1_1") (pintype "passive"))
      (node (ref "C55") (pin "2") (pinfunction "2_2") (pintype "passive"))
      (node (ref "C56") (pin "1") (pinfunction "1_1") (pintype "passive"))
      (node (ref "C57") (pin "2") (pinfunction "2_2") (pintype "passive"))
      (node (ref "C58") (pin "1") (pinfunction "1_1") (pintype "passive"))
      (node (ref "C59") (pin "2") (pinfunction "2_2") (pintype "passive"))
      (node (ref "C60") (pin "2") (pinfunction "2_2") (pintype "passive"))
      (node (ref "C61") (pin "1") (pinfunction "1_1") (pintype "passive"))
      (node (ref "C62") (pin "1") (pinfunction "1_1") (pintype "passive"))
      (node (ref "C63") (pin "2") (pinfunction "2_2") (pintype "passive"))
      (node (ref "C64") (pin "1") (pinfunction "1_1") (pintype "passive"))
      (node (ref "C65") (pin "2") (pinfunction "2_2") (pintype "passive"))
      (node (ref "C66") (pin "1") (pinfunction "1_1") (pintype "passive"))
      (node (ref "C67") (pin "2") (pinfunction "2_2") (pintype "passive"))
      (node (ref "C68") (pin "1") (pinfunction "1_1") (pintype "passive"))
      (node (ref "C69") (pin "2") (pinfunction "2_2") (pintype "passive"))
      (node (ref "C7") (pin "2") (pinfunction "2_2") (pintype "passive"))
      (node (ref "C70") (pin "1") (pinfunction "1_1") (pintype "passive"))
      (node (ref "C71") (pin "2") (pinfunction "2_2") (pintype "passive"))
      (node (ref "C8") (pin "2") (pinfunction "2_2") (pintype "passive"))
      (node (ref "C83") (pin "2") (pinfunction "2_2") (pintype "passive"))
      (node (ref "C84") (pin "2") (pinfunction "2_2") (pintype "passive"))
      (node (ref "C85") (pin "2") (pinfunction "2_2") (pintype "passive"))
      (node (ref "C86") (pin "2") (pinfunction "2_2") (pintype "passive"))
      (node (ref "C87") (pin "2") (pinfunction "2_2") (pintype "passive"))
      (node (ref "C88") (pin "2") (pinfunction "2_2") (pintype "passive"))
      (node (ref "C89") (pin "2") (pinfunction "2_2") (pintype "passive"))
      (node (ref "C9") (pin "1") (pinfunction "1_1") (pintype "passive"))
      (node (ref "C90") (pin "2") (pinfunction "2_2") (pintype "passive"))
      (node (ref "C91") (pin "2") (pinfunction "2_2") (pintype "passive"))
      (node (ref "C92") (pin "1") (pinfunction "1_1") (pintype "passive"))
      (node (ref "C93") (pin "1") (pinfunction "1_1") (pintype "passive"))
      (node (ref "C94") (pin "2") (pinfunction "2_2") (pintype "passive"))
      (node (ref "C95") (pin "1") (pinfunction "1_1") (pintype "passive"))
      (node (ref "C96") (pin "1") (pinfunction "1_1") (pintype "passive"))
      (node (ref "D2") (pin "1") (pinfunction "C_1") (pintype "passive"))
      (node (ref "D9") (pin "C") (pinfunction "C_C") (pintype "passive"))
      (node (ref "IC10") (pin "3") (pinfunction "IN+_3") (pintype "input"))
      (node (ref "IC6") (pin "2") (pinfunction "IN-_2") (pintype "input"))
      (node (ref "JP1") (pin "2") (pinfunction "2_2") (pintype "passive"))
      (node (ref "JP2") (pin "2") (pinfunction "2_2") (pintype "passive"))
      (node (ref "JP3") (pin "2") (pinfunction "2_2") (pintype "passive"))
      (node (ref "JP4") (pin "1") (pinfunction "1_1") (pintype "passive"))
      (node (ref "R1") (pin "E") (pinfunction "3_E") (pintype "passive"))
      (node (ref "R16") (pin "1") (pinfunction "1_1") (pintype "passive"))
      (node (ref "R17") (pin "1") (pinfunction "1_1") (pintype "passive"))
      (node (ref "R18") (pin "2") (pinfunction "2_2") (pintype "passive"))
      (node (ref "R24") (pin "1") (pinfunction "1_1") (pintype "passive"))
      (node (ref "R31") (pin "1") (pinfunction "1_1") (pintype "passive"))
      (node (ref "R32") (pin "1") (pinfunction "1_1") (pintype "passive"))
      (node (ref "R39") (pin "1") (pinfunction "1_1") (pintype "passive"))
      (node (ref "R4") (pin "2") (pinfunction "2_2") (pintype "passive"))
      (node (ref "R5") (pin "2") (pinfunction "2_2") (pintype "passive"))
      (node (ref "R53") (pin "A") (pinfunction "1_A") (pintype "passive"))
      (node (ref "R9") (pin "A") (pinfunction "1_A") (pintype "passive"))
      (node (ref "S2") (pin "1") (pinfunction "1_1") (pintype "bidirectional"))
      (node (ref "S3") (pin "3") (pinfunction "3_3") (pintype "passive"))
      (node (ref "TP2") (pin "P$1") (pinfunction "P$1_P$1") (pintype "bidirectional"))
      (node (ref "X1") (pin "2") (pinfunction "2_2") (pintype "passive"))
      (node (ref "X5") (pin "2") (pinfunction "S_2") (pintype "passive"))
      (node (ref "X7") (pin "2") (pinfunction "S_2") (pintype "passive"))
    )
    (net (code "6") (name "Net-(C5-Pad1)") (class "Default")
      (node (ref "C5") (pin "1") (pinfunction "1_1") (pintype "passive"))
      (node (ref "D5") (pin "A") (pinfunction "A_A") (pintype "passive"))
      (node (ref "D6") (pin "C") (pinfunction "C_C") (pintype "passive"))
      (node (ref "R62") (pin "1") (pinfunction "1_1") (pintype "passive"))
      (node (ref "R64") (pin "2") (pinfunction "2_2") (pintype "passive"))
    )
    (net (code "7") (name "Net-(C6-Pad1)") (class "Default")
      (node (ref "C6") (pin "1") (pinfunction "1_1") (pintype "passive"))
      (node (ref "D7") (pin "A") (pinfunction "A_A") (pintype "passive"))
      (node (ref "D8") (pin "C") (pinfunction "C_C") (pintype "passive"))
      (node (ref "R63") (pin "1") (pinfunction "1_1") (pintype "passive"))
      (node (ref "R65") (pin "2") (pinfunction "2_2") (pintype "passive"))
    )
    (net (code "8") (name "Net-(C22-Pad1)") (class "Default")
      (node (ref "C22") (pin "1") (pinfunction "1_1") (pintype "passive"))
      (node (ref "S2") (pin "2") (pinfunction "2_2") (pintype "bidirectional"))
    )
    (net (code "9") (name "Net-(C71-Pad1)") (class "Default")
      (node (ref "C71") (pin "1") (pinfunction "1_1") (pintype "passive"))
      (node (ref "S2") (pin "3") (pinfunction "3_3") (pintype "bidirectional"))
    )
    (net (code "10") (name "Net-(C72-Pad1)") (class "Default")
      (node (ref "C72") (pin "1") (pinfunction "1_1") (pintype "passive"))
      (node (ref "S1") (pin "2") (pinfunction "2_2") (pintype "bidirectional"))
    )
    (net (code "11") (name "Net-(C73-Pad1)") (class "Default")
      (node (ref "C73") (pin "1") (pinfunction "1_1") (pintype "passive"))
      (node (ref "S1") (pin "3") (pinfunction "3_3") (pintype "bidirectional"))
    )
    (net (code "12") (name "Net-(C74-Pad1)") (class "Default")
      (node (ref "C74") (pin "1") (pinfunction "1_1") (pintype "passive"))
      (node (ref "S1") (pin "4") (pinfunction "4_4") (pintype "bidirectional"))
    )
    (net (code "13") (name "Net-(C75-Pad1)") (class "Default")
      (node (ref "C75") (pin "1") (pinfunction "1_1") (pintype "passive"))
      (node (ref "S1") (pin "5") (pinfunction "5_5") (pintype "bidirectional"))
    )
    (net (code "14") (name "Net-(C76-Pad1)") (class "Default")
      (node (ref "C76") (pin "1") (pinfunction "1_1") (pintype "passive"))
      (node (ref "S1") (pin "6") (pinfunction "6_6") (pintype "bidirectional"))
    )
    (net (code "15") (name "Net-(C77-Pad1)") (class "Default")
      (node (ref "C77") (pin "1") (pinfunction "1_1") (pintype "passive"))
      (node (ref "S1") (pin "7") (pinfunction "7_7") (pintype "bidirectional"))
    )
    (net (code "16") (name "Net-(C78-Pad1)") (class "Default")
      (node (ref "C78") (pin "1") (pinfunction "1_1") (pintype "passive"))
      (node (ref "S1") (pin "8") (pinfunction "8_8") (pintype "bidirectional"))
    )
    (net (code "17") (name "Net-(C79-Pad1)") (class "Default")
      (node (ref "C79") (pin "1") (pinfunction "1_1") (pintype "passive"))
      (node (ref "S1") (pin "9") (pinfunction "9_9") (pintype "bidirectional"))
    )
    (net (code "18") (name "Net-(C80-Pad1)") (class "Default")
      (node (ref "C80") (pin "1") (pinfunction "1_1") (pintype "passive"))
      (node (ref "S1") (pin "10") (pinfunction "10_10") (pintype "bidirectional"))
    )
    (net (code "19") (name "Net-(C81-Pad1)") (class "Default")
      (node (ref "C81") (pin "1") (pinfunction "1_1") (pintype "passive"))
      (node (ref "S1") (pin "11") (pinfunction "11_11") (pintype "bidirectional"))
    )
    (net (code "20") (name "Net-(C82-Pad1)") (class "Default")
      (node (ref "C82") (pin "1") (pinfunction "1_1") (pintype "passive"))
      (node (ref "S1") (pin "12") (pinfunction "12_12") (pintype "bidirectional"))
    )
    (net (code "21") (name "Net-(C83-Pad1)") (class "Default")
      (node (ref "C83") (pin "1") (pinfunction "1_1") (pintype "passive"))
      (node (ref "S2") (pin "4") (pinfunction "4_4") (pintype "bidirectional"))
    )
    (net (code "22") (name "Net-(C84-Pad1)") (class "Default")
      (node (ref "C84") (pin "1") (pinfunction "1_1") (pintype "passive"))
      (node (ref "S2") (pin "5") (pinfunction "5_5") (pintype "bidirectional"))
    )
    (net (code "23") (name "Net-(C85-Pad1)") (class "Default")
      (node (ref "C85") (pin "1") (pinfunction "1_1") (pintype "passive"))
      (node (ref "S2") (pin "6") (pinfunction "6_6") (pintype "bidirectional"))
    )
    (net (code "24") (name "Net-(C86-Pad1)") (class "Default")
      (node (ref "C86") (pin "1") (pinfunction "1_1") (pintype "passive"))
      (node (ref "S2") (pin "7") (pinfunction "7_7") (pintype "bidirectional"))
    )
    (net (code "25") (name "Net-(C87-Pad1)") (class "Default")
      (node (ref "C87") (pin "1") (pinfunction "1_1") (pintype "passive"))
      (node (ref "S2") (pin "8") (pinfunction "8_8") (pintype "bidirectional"))
    )
    (net (code "26") (name "Net-(C88-Pad1)") (class "Default")
      (node (ref "C88") (pin "1") (pinfunction "1_1") (pintype "passive"))
      (node (ref "S2") (pin "9") (pinfunction "9_9") (pintype "bidirectional"))
    )
    (net (code "27") (name "Net-(C89-Pad1)") (class "Default")
      (node (ref "C89") (pin "1") (pinfunction "1_1") (pintype "passive"))
      (node (ref "S2") (pin "10") (pinfunction "10_10") (pintype "bidirectional"))
    )
    (net (code "28") (name "Net-(C90-Pad1)") (class "Default")
      (node (ref "C90") (pin "1") (pinfunction "1_1") (pintype "passive"))
      (node (ref "S2") (pin "11") (pinfunction "11_11") (pintype "bidirectional"))
    )
    (net (code "29") (name "Net-(C91-Pad1)") (class "Default")
      (node (ref "C91") (pin "1") (pinfunction "1_1") (pintype "passive"))
      (node (ref "S2") (pin "12") (pinfunction "12_12") (pintype "bidirectional"))
    )
    (net (code "30") (name "Net-(D1-PadA)") (class "Default")
      (node (ref "D1") (pin "A") (pinfunction "A_A") (pintype "passive"))
      (node (ref "R2") (pin "1") (pinfunction "1_1") (pintype "passive"))
      (node (ref "R3") (pin "2") (pinfunction "2_2") (pintype "passive"))
    )
    (net (code "31") (name "Net-(D1-PadC)") (class "Default")
      (node (ref "D1") (pin "C") (pinfunction "C_C") (pintype "passive"))
      (node (ref "D4") (pin "A") (pinfunction "A_A") (pintype "passive"))
      (node (ref "R2") (pin "2") (pinfunction "2_2") (pintype "passive"))
      (node (ref "S3") (pin "2") (pinfunction "2_2") (pintype "passive"))
    )
    (net (code "32") (name "Net-(D2-A)") (class "Default")
      (node (ref "C1") (pin "2") (pinfunction "2_2") (pintype "passive"))
      (node (ref "D2") (pin "2") (pinfunction "A_2") (pintype "passive"))
      (node (ref "R53") (pin "E") (pinfunction "3_E") (pintype "passive"))
      (node (ref "R7") (pin "2") (pinfunction "2_2") (pintype "passive"))
      (node (ref "R9") (pin "E") (pinfunction "3_E") (pintype "passive"))
    )
    (net (code "33") (name "Net-(D4-PadC)") (class "Default")
      (node (ref "D4") (pin "C") (pinfunction "C_C") (pintype "passive"))
      (node (ref "R60") (pin "2") (pinfunction "2_2") (pintype "passive"))
    )
    (net (code "34") (name "Net-(D9-PadA)") (class "Default")
      (node (ref "D9") (pin "A") (pinfunction "A_A") (pintype "passive"))
      (node (ref "R66") (pin "1") (pinfunction "1_1") (pintype "passive"))
    )
    (net (code "35") (name "Net-(D12-1)") (class "Default")
      (node (ref "D12") (pin "A") (pinfunction "1_A") (pintype "passive"))
      (node (ref "R58") (pin "1") (pinfunction "1_1") (pintype "passive"))
      (node (ref "X4") (pin "2") (pinfunction "2_2") (pintype "passive"))
      (node (ref "X4") (pin "3") (pinfunction "2_3") (pintype "passive"))
      (node (ref "X4") (pin "4") (pinfunction "2_4") (pintype "passive"))
      (node (ref "X4") (pin "5") (pinfunction "2_5") (pintype "passive"))
    )
    (net (code "36") (name "Net-(D12-2)") (class "Default")
      (node (ref "C6") (pin "2") (pinfunction "2_2") (pintype "passive"))
      (node (ref "D12") (pin "C") (pinfunction "2_C") (pintype "passive"))
      (node (ref "R65") (pin "1") (pinfunction "1_1") (pintype "passive"))
      (node (ref "X4") (pin "1") (pinfunction "1_1") (pintype "passive"))
    )
    (net (code "37") (name "Net-(D13-1)") (class "Default")
      (node (ref "D13") (pin "A") (pinfunction "1_A") (pintype "passive"))
      (node (ref "R6") (pin "1") (pinfunction "1_1") (pintype "passive"))
      (node (ref "X2") (pin "2") (pinfunction "2_2") (pintype "passive"))
      (node (ref "X2") (pin "3") (pinfunction "2_3") (pintype "passive"))
      (node (ref "X2") (pin "4") (pinfunction "2_4") (pintype "passive"))
      (node (ref "X2") (pin "5") (pinfunction "2_5") (pintype "passive"))
    )
    (net (code "38") (name "Net-(D13-2)") (class "Default")
      (node (ref "C5") (pin "2") (pinfunction "2_2") (pintype "passive"))
      (node (ref "D13") (pin "C") (pinfunction "2_C") (pintype "passive"))
      (node (ref "R64") (pin "1") (pinfunction "1_1") (pintype "passive"))
      (node (ref "X2") (pin "1") (pinfunction "1_1") (pintype "passive"))
    )
    (net (code "39") (name "Net-(D14-PadA)") (class "Default")
      (node (ref "D14") (pin "A") (pinfunction "A_A") (pintype "passive"))
      (node (ref "R18") (pin "1") (pinfunction "1_1") (pintype "passive"))
    )
    (net (code "40") (name "Net-(IC1-IN+)") (class "Default")
      (node (ref "IC1") (pin "3") (pinfunction "IN+_3") (pintype "input"))
      (node (ref "R20") (pin "1") (pinfunction "1_1") (pintype "passive"))
      (node (ref "R24") (pin "2") (pinfunction "2_2") (pintype "passive"))
    )
    (net (code "41") (name "Net-(IC1-IN-)") (class "Default")
      (node (ref "IC1") (pin "2") (pinfunction "IN-_2") (pintype "input"))
      (node (ref "R19") (pin "1") (pinfunction "1_1") (pintype "passive"))
      (node (ref "R23") (pin "2") (pinfunction "2_2") (pintype "passive"))
    )
    (net (code "42") (name "Net-(IC1-OUT)") (class "Default")
      (node (ref "IC1") (pin "6") (pinfunction "OUT_6") (pintype "output"))
      (node (ref "R23") (pin "1") (pinfunction "1_1") (pintype "passive"))
      (node (ref "R25") (pin "2") (pinfunction "2_2") (pintype "passive"))
      (node (ref "R40") (pin "2") (pinfunction "2_2") (pintype "passive"))
    )
    (net (code "43") (name "Net-(IC2-COMP)") (class "Default")
      (node (ref "C13") (pin "1") (pinfunction "1_1") (pintype "passive"))
      (node (ref "IC2") (pin "8") (pinfunction "COMP_8") (pintype "passive"))
    )
    (net (code "44") (name "Net-(IC2-IN+)") (class "Default")
      (node (ref "C10") (pin "1") (pinfunction "1_1") (pintype "passive"))
      (node (ref "IC2") (pin "3") (pinfunction "IN+_3") (pintype "input"))
      (node (ref "JP4") (pin "2") (pinfunction "2_2") (pintype "passive"))
      (node (ref "R14") (pin "2") (pinfunction "2_2") (pintype "passive"))
      (node (ref "R16") (pin "2") (pinfunction "2_2") (pintype "passive"))
      (node (ref "R70") (pin "2") (pinfunction "SA_2") (pintype "passive"))
      (node (ref "X6") (pin "2") (pinfunction "S_2") (pintype "passive"))
    )
    (net (code "45") (name "Net-(IC2-IN-)") (class "Default")
      (node (ref "C14") (pin "1") (pinfunction "1_1") (pintype "passive"))
      (node (ref "IC2") (pin "2") (pinfunction "IN-_2") (pintype "input"))
      (node (ref "R13") (pin "2") (pinfunction "2_2") (pintype "passive"))
      (node (ref "R21") (pin "2") (pinfunction "2_2") (pintype "passive"))
    )
    (net (code "46") (name "Net-(IC2-OUT)") (class "Default")
      (node (ref "C13") (pin "2") (pinfunction "2_2") (pintype "passive"))
      (node (ref "C14") (pin "2") (pinfunction "2_2") (pintype "passive"))
      (node (ref "IC2") (pin "6") (pinfunction "OUT_6") (pintype "output"))
      (node (ref "R19") (pin "2") (pinfunction "2_2") (pintype "passive"))
      (node (ref "R21") (pin "1") (pinfunction "1_1") (pintype "passive"))
    )
    (net (code "47") (name "Net-(IC3-IN)") (class "Default")
      (node (ref "IC3") (pin "3") (pinfunction "IN_3") (pintype "input"))
      (node (ref "R57") (pin "1") (pinfunction "1_1") (pintype "passive"))
    )
    (net (code "48") (name "Net-(IC3-OUT)") (class "Default")
      (node (ref "IC3") (pin "6") (pinfunction "OUT_6") (pintype "output"))
      (node (ref "R63") (pin "2") (pinfunction "2_2") (pintype "passive"))
    )
    (net (code "49") (name "Net-(IC4-COMP)") (class "Default")
      (node (ref "C12") (pin "1") (pinfunction "1_1") (pintype "passive"))
      (node (ref "IC4") (pin "8") (pinfunction "COMP_8") (pintype "passive"))
    )
    (net (code "50") (name "Net-(IC4-IN+)") (class "Default")
      (node (ref "C11") (pin "1") (pinfunction "1_1") (pintype "passive"))
      (node (ref "IC4") (pin "3") (pinfunction "IN+_3") (pintype "input"))
      (node (ref "JP3") (pin "1") (pinfunction "1_1") (pintype "passive"))
      (node (ref "R15") (pin "1") (pinfunction "1_1") (pintype "passive"))
      (node (ref "R17") (pin "2") (pinfunction "2_2") (pintype "passive"))
      (node (ref "R70") (pin "3") (pinfunction "SB_3") (pintype "passive"))
      (node (ref "X6") (pin "3") (pinfunction "S_3") (pintype "passive"))
    )
    (net (code "51") (name "Net-(IC4-IN-)") (class "Default")
      (node (ref "C15") (pin "1") (pinfunction "1_1") (pintype "passive"))
      (node (ref "IC4") (pin "2") (pinfunction "IN-_2") (pintype "input"))
      (node (ref "R13") (pin "1") (pinfunction "1_1") (pintype "passive"))
      (node (ref "R22") (pin "2") (pinfunction "2_2") (pintype "passive"))
    )
    (net (code "52") (name "Net-(IC4-OUT)") (class "Default")
      (node (ref "C12") (pin "2") (pinfunction "2_2") (pintype "passive"))
      (node (ref "C15") (pin "2") (pinfunction "2_2") (pintype "passive"))
      (node (ref "IC4") (pin "6") (pinfunction "OUT_6") (pintype "output"))
      (node (ref "R20") (pin "2") (pinfunction "2_2") (pintype "passive"))
      (node (ref "R22") (pin "1") (pinfunction "1_1") (pintype "passive"))
    )
    (net (code "53") (name "Net-(IC5-IN+)") (class "Default")
      (node (ref "IC5") (pin "3") (pinfunction "IN+_3") (pintype "input"))
      (node (ref "R42") (pin "1") (pinfunction "1_1") (pintype "passive"))
    )
    (net (code "54") (name "Net-(IC5-IN-)") (class "Default")
      (node (ref "IC5") (pin "2") (pinfunction "IN-_2") (pintype "input"))
      (node (ref "R43") (pin "2") (pinfunction "2_2") (pintype "passive"))
    )
    (net (code "55") (name "Net-(IC5-OUT)") (class "Default")
      (node (ref "C72") (pin "2") (pinfunction "2_2") (pintype "passive"))
      (node (ref "C73") (pin "2") (pinfunction "2_2") (pintype "passive"))
      (node (ref "C74") (pin "2") (pinfunction "2_2") (pintype "passive"))
      (node (ref "C75") (pin "2") (pinfunction "2_2") (pintype "passive"))
      (node (ref "C76") (pin "2") (pinfunction "2_2") (pintype "passive"))
      (node (ref "C77") (pin "2") (pinfunction "2_2") (pintype "passive"))
      (node (ref "C78") (pin "2") (pinfunction "2_2") (pintype "passive"))
      (node (ref "C79") (pin "2") (pinfunction "2_2") (pintype "passive"))
      (node (ref "C80") (pin "2") (pinfunction "2_2") (pintype "passive"))
      (node (ref "C81") (pin "2") (pinfunction "2_2") (pintype "passive"))
      (node (ref "C82") (pin "2") (pinfunction "2_2") (pintype "passive"))
      (node (ref "IC5") (pin "6") (pinfunction "OUT_6") (pintype "output"))
      (node (ref "R45") (pin "2") (pinfunction "2_2") (pintype "passive"))
      (node (ref "S1") (pin "1") (pinfunction "1_1") (pintype "bidirectional"))
    )
    (net (code "56") (name "Net-(IC6-IN+)") (class "Default")
      (node (ref "IC6") (pin "3") (pinfunction "IN+_3") (pintype "input"))
      (node (ref "R25") (pin "1") (pinfunction "1_1") (pintype "passive"))
    )
    (net (code "57") (name "Net-(IC6-OUT)") (class "Default")
      (node (ref "IC6") (pin "6") (pinfunction "OUT_6") (pintype "output"))
      (node (ref "R27") (pin "2") (pinfunction "2_2") (pintype "passive"))
    )
    (net (code "58") (name "Net-(IC7-COMP)") (class "Default")
      (node (ref "C19") (pin "1") (pinfunction "1_1") (pintype "passive"))
      (node (ref "IC7") (pin "8") (pinfunction "COMP_8") (pintype "passive"))
    )
    (net (code "59") (name "Net-(IC7-IN+)") (class "Default")
      (node (ref "C16") (pin "1") (pinfunction "1_1") (pintype "passive"))
      (node (ref "IC7") (pin "3") (pinfunction "IN+_3") (pintype "input"))
      (node (ref "R29") (pin "2") (pinfunction "2_2") (pintype "passive"))
      (node (ref "R31") (pin "2") (pinfunction "2_2") (pintype "passive"))
    )
    (net (code "60") (name "Net-(IC7-IN-)") (class "Default")
      (node (ref "C20") (pin "1") (pinfunction "1_1") (pintype "passive"))
      (node (ref "IC7") (pin "2") (pinfunction "IN-_2") (pintype "input"))
      (node (ref "R28") (pin "2") (pinfunction "2_2") (pintype "passive"))
      (node (ref "R36") (pin "2") (pinfunction "2_2") (pintype "passive"))
    )
    (net (code "61") (name "Net-(IC7-OUT)") (class "Default")
      (node (ref "C19") (pin "2") (pinfunction "2_2") (pintype "passive"))
      (node (ref "C20") (pin "2") (pinfunction "2_2") (pintype "passive"))
      (node (ref "IC7") (pin "6") (pinfunction "OUT_6") (pintype "output"))
      (node (ref "R34") (pin "2") (pinfunction "2_2") (pintype "passive"))
      (node (ref "R36") (pin "1") (pinfunction "1_1") (pintype "passive"))
    )
    (net (code "62") (name "Net-(IC8-COMP)") (class "Default")
      (node (ref "C18") (pin "1") (pinfunction "1_1") (pintype "passive"))
      (node (ref "IC8") (pin "8") (pinfunction "COMP_8") (pintype "passive"))
    )
    (net (code "63") (name "Net-(IC8-IN+)") (class "Default")
      (node (ref "C17") (pin "1") (pinfunction "1_1") (pintype "passive"))
      (node (ref "IC8") (pin "3") (pinfunction "IN+_3") (pintype "input"))
      (node (ref "R30") (pin "1") (pinfunction "1_1") (pintype "passive"))
      (node (ref "R32") (pin "2") (pinfunction "2_2") (pintype "passive"))
    )
    (net (code "64") (name "Net-(IC8-IN-)") (class "Default")
      (node (ref "C21") (pin "1") (pinfunction "1_1") (pintype "passive"))
      (node (ref "IC8") (pin "2") (pinfunction "IN-_2") (pintype "input"))
      (node (ref "R28") (pin "1") (pinfunction "1_1") (pintype "passive"))
      (node (ref "R37") (pin "2") (pinfunction "2_2") (pintype "passive"))
    )
    (net (code "65") (name "Net-(IC8-OUT)") (class "Default")
      (node (ref "C18") (pin "2") (pinfunction "2_2") (pintype "passive"))
      (node (ref "C21") (pin "2") (pinfunction "2_2") (pintype "passive"))
      (node (ref "IC8") (pin "6") (pinfunction "OUT_6") (pintype "output"))
      (node (ref "R35") (pin "2") (pinfunction "2_2") (pintype "passive"))
      (node (ref "R37") (pin "1") (pinfunction "1_1") (pintype "passive"))
    )
    (net (code "66") (name "Net-(IC9-IN+)") (class "Default")
      (node (ref "IC9") (pin "3") (pinfunction "IN+_3") (pintype "input"))
      (node (ref "R35") (pin "1") (pinfunction "1_1") (pintype "passive"))
      (node (ref "R39") (pin "2") (pinfunction "2_2") (pintype "passive"))
    )
    (net (code "67") (name "Net-(IC9-IN-)") (class "Default")
      (node (ref "IC9") (pin "2") (pinfunction "IN-_2") (pintype "input"))
      (node (ref "R34") (pin "1") (pinfunction "1_1") (pintype "passive"))
      (node (ref "R38") (pin "2") (pinfunction "2_2") (pintype "passive"))
    )
    (net (code "68") (name "Net-(IC9-OUT)") (class "Default")
      (node (ref "IC9") (pin "6") (pinfunction "OUT_6") (pintype "output"))
      (node (ref "R33") (pin "2") (pinfunction "2_2") (pintype "passive"))
      (node (ref "R38") (pin "1") (pinfunction "1_1") (pintype "passive"))
      (node (ref "TP1") (pin "P$1") (pinfunction "P$1_P$1") (pintype "bidirectional"))
    )
    (net (code "69") (name "Net-(IC10-IN-)") (class "Default")
      (node (ref "IC10") (pin "2") (pinfunction "IN-_2") (pintype "input"))
      (node (ref "R33") (pin "1") (pinfunction "1_1") (pintype "passive"))
      (node (ref "R40") (pin "1") (pinfunction "1_1") (pintype "passive"))
      (node (ref "R41") (pin "2") (pinfunction "2_2") (pintype "passive"))
    )
    (net (code "70") (name "Net-(IC10-OUT)") (class "Default")
      (node (ref "IC10") (pin "6") (pinfunction "OUT_6") (pintype "output"))
      (node (ref "R0") (pin "2") (pinfunction "2_2") (pintype "passive"))
      (node (ref "R0") (pin "3") (pinfunction "3_3") (pintype "passive"))
      (node (ref "R42") (pin "2") (pinfunction "2_2") (pintype "passive"))
    )
    (net (code "71") (name "Net-(IC11-IN+)") (class "Default")
      (node (ref "IC11") (pin "3") (pinfunction "IN+_3") (pintype "input"))
      (node (ref "R45") (pin "1") (pinfunction "1_1") (pintype "passive"))
      (node (ref "R46") (pin "1") (pinfunction "1_1") (pintype "passive"))
    )
    (net (code "72") (name "Net-(IC11-IN-)") (class "Default")
      (node (ref "IC11") (pin "2") (pinfunction "IN-_2") (pintype "input"))
      (node (ref "R47") (pin "2") (pinfunction "2_2") (pintype "passive"))
    )
    (net (code "73") (name "Net-(IC11-OUT)") (class "Default")
      (node (ref "IC11") (pin "6") (pinfunction "OUT_6") (pintype "output"))
      (node (ref "R48") (pin "1") (pinfunction "1_1") (pintype "passive"))
      (node (ref "R50") (pin "A") (pinfunction "1_A") (pintype "passive"))
      (node (ref "R50") (pin "S") (pinfunction "2_S") (pintype "passive"))
    )
    (net (code "74") (name "Net-(IC12-IN+)") (class "Default")
      (node (ref "C23") (pin "1") (pinfunction "1_1") (pintype "passive"))
      (node (ref "IC12") (pin "3") (pinfunction "IN+_3") (pintype "input"))
      (node (ref "R52") (pin "1") (pinfunction "1_1") (pintype "passive"))
    )
    (net (code "75") (name "Net-(IC12-IN-)") (class "Default")
      (node (ref "IC12") (pin "2") (pinfunction "IN-_2") (pintype "input"))
      (node (ref "IC12") (pin "6") (pinfunction "OUT_6") (pintype "output"))
      (node (ref "S3") (pin "1") (pinfunction "1_1") (pintype "passive"))
    )
    (net (code "76") (name "Net-(IC13-IN+)") (class "Default")
      (node (ref "IC13") (pin "3") (pinfunction "IN+_3") (pintype "input"))
      (node (ref "R4") (pin "1") (pinfunction "1_1") (pintype "passive"))
      (node (ref "R5") (pin "1") (pinfunction "1_1") (pintype "passive"))
      (node (ref "R6") (pin "2") (pinfunction "2_2") (pintype "passive"))
    )
    (net (code "77") (name "Net-(IC13-IN-)") (class "Default")
      (node (ref "IC13") (pin "2") (pinfunction "IN-_2") (pintype "input"))
      (node (ref "R3") (pin "1") (pinfunction "1_1") (pintype "passive"))
      (node (ref "R55") (pin "1") (pinfunction "1_1") (pintype "passive"))
      (node (ref "R8") (pin "2") (pinfunction "2_2") (pintype "passive"))
    )
    (net (code "78") (name "Net-(IC13-OUT)") (class "Default")
      (node (ref "IC13") (pin "6") (pinfunction "OUT_6") (pintype "output"))
      (node (ref "R61") (pin "2") (pinfunction "2_2") (pintype "passive"))
      (node (ref "R8") (pin "1") (pinfunction "1_1") (pintype "passive"))
    )
    (net (code "79") (name "Net-(IC14-IN+)") (class "Default")
      (node (ref "C2") (pin "2") (pinfunction "2_2") (pintype "passive"))
      (node (ref "IC14") (pin "3") (pinfunction "IN+_3") (pintype "input"))
      (node (ref "R9") (pin "S") (pinfunction "2_S") (pintype "passive"))
    )
    (net (code "80") (name "Net-(IC15-IN+)") (class "Default")
      (node (ref "C4") (pin "2") (pinfunction "2_2") (pintype "passive"))
      (node (ref "IC15") (pin "3") (pinfunction "IN+_3") (pintype "input"))
      (node (ref "R53") (pin "S") (pinfunction "2_S") (pintype "passive"))
    )
    (net (code "81") (name "Net-(IC16-IN+)") (class "Default")
      (node (ref "IC16") (pin "3") (pinfunction "IN+_3") (pintype "input"))
      (node (ref "R58") (pin "2") (pinfunction "2_2") (pintype "passive"))
      (node (ref "R60") (pin "1") (pinfunction "1_1") (pintype "passive"))
    )
    (net (code "82") (name "Net-(IC16-IN-)") (class "Default")
      (node (ref "IC16") (pin "2") (pinfunction "IN-_2") (pintype "input"))
      (node (ref "R56") (pin "1") (pinfunction "1_1") (pintype "passive"))
      (node (ref "R59") (pin "2") (pinfunction "2_2") (pintype "passive"))
    )
    (net (code "83") (name "Net-(IC16-OUT)") (class "Default")
      (node (ref "IC16") (pin "6") (pinfunction "OUT_6") (pintype "output"))
      (node (ref "R57") (pin "2") (pinfunction "2_2") (pintype "passive"))
      (node (ref "R59") (pin "1") (pinfunction "1_1") (pintype "passive"))
    )
    (net (code "84") (name "Net-(IC17-IN)") (class "Default")
      (node (ref "IC17") (pin "3") (pinfunction "IN_3") (pintype "input"))
      (node (ref "R61") (pin "1") (pinfunction "1_1") (pintype "passive"))
    )
    (net (code "85") (name "Net-(IC17-OUT)") (class "Default")
      (node (ref "IC17") (pin "6") (pinfunction "OUT_6") (pintype "output"))
      (node (ref "R62") (pin "2") (pinfunction "2_2") (pintype "passive"))
    )
    (net (code "86") (name "Net-(JP1-Pad1)") (class "Default")
      (node (ref "JP1") (pin "1") (pinfunction "1_1") (pintype "passive"))
      (node (ref "R10") (pin "1") (pinfunction "1_1") (pintype "passive"))
      (node (ref "R55") (pin "2") (pinfunction "2_2") (pintype "passive"))
    )
    (net (code "87") (name "Net-(JP2-Pad1)") (class "Default")
      (node (ref "JP2") (pin "1") (pinfunction "1_1") (pintype "passive"))
      (node (ref "R54") (pin "1") (pinfunction "1_1") (pintype "passive"))
      (node (ref "R56") (pin "2") (pinfunction "2_2") (pintype "passive"))
    )
    (net (code "88") (name "Net-(R0-Pad1)") (class "Default")
      (node (ref "R0") (pin "1") (pinfunction "1_1") (pintype "passive"))
      (node (ref "R41") (pin "1") (pinfunction "1_1") (pintype "passive"))
    )
    (net (code "89") (name "Net-(R1-1)") (class "Default")
      (node (ref "R1") (pin "A") (pinfunction "1_A") (pintype "passive"))
      (node (ref "R1") (pin "S") (pinfunction "2_S") (pintype "passive"))
      (node (ref "R44") (pin "1") (pinfunction "1_1") (pintype "passive"))
    )
    (net (code "90") (name "Net-(R27-Pad1)") (class "Default")
      (node (ref "R27") (pin "1") (pinfunction "1_1") (pintype "passive"))
      (node (ref "X1") (pin "1") (pinfunction "1_1") (pintype "passive"))
    )
    (net (code "91") (name "Net-(R29-Pad1)") (class "Default")
      (node (ref "R29") (pin "1") (pinfunction "1_1") (pintype "passive"))
      (node (ref "X3") (pin "1") (pinfunction "1_1") (pintype "passive"))
    )
    (net (code "92") (name "Net-(R30-Pad2)") (class "Default")
      (node (ref "R30") (pin "2") (pinfunction "2_2") (pintype "passive"))
      (node (ref "X3") (pin "2") (pinfunction "2_2") (pintype "passive"))
    )
    (net (code "93") (name "Net-(R43-Pad1)") (class "Default")
      (node (ref "R43") (pin "1") (pinfunction "1_1") (pintype "passive"))
      (node (ref "R44") (pin "2") (pinfunction "2_2") (pintype "passive"))
      (node (ref "S1") (pin "13") (pinfunction "13_13") (pintype "bidirectional"))
    )
    (net (code "94") (name "Net-(R47-Pad1)") (class "Default")
      (node (ref "R47") (pin "1") (pinfunction "1_1") (pintype "passive"))
      (node (ref "R48") (pin "2") (pinfunction "2_2") (pintype "passive"))
      (node (ref "R49") (pin "2") (pinfunction "2_2") (pintype "passive"))
    )
    (net (code "95") (name "Net-(R50-3)") (class "Default")
      (node (ref "R50") (pin "E") (pinfunction "3_E") (pintype "passive"))
      (node (ref "R52") (pin "2") (pinfunction "2_2") (pintype "passive"))
    )
    (net (code "96") (name "Net-(R51-1)") (class "Default")
      (node (ref "R49") (pin "1") (pinfunction "1_1") (pintype "passive"))
      (node (ref "R51") (pin "A") (pinfunction "1_A") (pintype "passive"))
      (node (ref "R51") (pin "S") (pinfunction "2_S") (pintype "passive"))
    )
    (net (code "97") (name "Net-(R51-3)") (class "Default")
      (node (ref "R51") (pin "E") (pinfunction "3_E") (pintype "passive"))
      (node (ref "S2") (pin "13") (pinfunction "13_13") (pintype "bidirectional"))
    )
    (net (code "98") (name "Net-(R70-A)") (class "Default")
      (node (ref "R14") (pin "1") (pinfunction "1_1") (pintype "passive"))
      (node (ref "R70") (pin "1") (pinfunction "A_1") (pintype "passive"))
    )
    (net (code "99") (name "Net-(R70-B)") (class "Default")
      (node (ref "R15") (pin "2") (pinfunction "2_2") (pintype "passive"))
      (node (ref "R70") (pin "4") (pinfunction "B_4") (pintype "passive"))
    )
    (net (code "100") (name "unconnected-(IC2-OFF-Pad1)") (class "Default")
      (node (ref "IC2") (pin "1") (pinfunction "OFF_1") (pintype "passive"))
    )
    (net (code "101") (name "unconnected-(IC2-OFF-Pad5)") (class "Default")
      (node (ref "IC2") (pin "5") (pinfunction "OFF_5") (pintype "passive"))
    )
    (net (code "102") (name "unconnected-(IC3-BW-Pad1)") (class "Default")
      (node (ref "IC3") (pin "1") (pinfunction "BW_1") (pintype "passive"))
    )
    (net (code "103") (name "unconnected-(IC4-OFF-Pad1)") (class "Default")
      (node (ref "IC4") (pin "1") (pinfunction "OFF_1") (pintype "passive"))
    )
    (net (code "104") (name "unconnected-(IC4-OFF-Pad5)") (class "Default")
      (node (ref "IC4") (pin "5") (pinfunction "OFF_5") (pintype "passive"))
    )
    (net (code "105") (name "unconnected-(IC7-OFF-Pad1)") (class "Default")
      (node (ref "IC7") (pin "1") (pinfunction "OFF_1") (pintype "passive"))
    )
    (net (code "106") (name "unconnected-(IC7-OFF-Pad5)") (class "Default")
      (node (ref "IC7") (pin "5") (pinfunction "OFF_5") (pintype "passive"))
    )
    (net (code "107") (name "unconnected-(IC8-OFF-Pad1)") (class "Default")
      (node (ref "IC8") (pin "1") (pinfunction "OFF_1") (pintype "passive"))
    )
    (net (code "108") (name "unconnected-(IC8-OFF-Pad5)") (class "Default")
      (node (ref "IC8") (pin "5") (pinfunction "OFF_5") (pintype "passive"))
    )
    (net (code "109") (name "unconnected-(IC17-BW-Pad1)") (class "Default")
      (node (ref "IC17") (pin "1") (pinfunction "BW_1") (pintype "passive"))
    )
    (net (code "110") (name "unconnected-(Q1-D-Pad4)") (class "Default")
      (node (ref "Q1") (pin "4") (pinfunction "D_4") (pintype "passive"))
    )
    (net (code "111") (name "unconnected-(Q1-G-Pad1)") (class "Default")
      (node (ref "Q1") (pin "1") (pinfunction "G_1") (pintype "passive"))
    )
    (net (code "112") (name "unconnected-(Q1-S-Pad3)") (class "Default")
      (node (ref "Q1") (pin "3") (pinfunction "S_3") (pintype "passive"))
    )
    (net (code "113") (name "unconnected-(Q2-D-Pad4)") (class "Default")
      (node (ref "Q2") (pin "4") (pinfunction "D_4") (pintype "passive"))
    )
    (net (code "114") (name "unconnected-(Q2-G-Pad1)") (class "Default")
      (node (ref "Q2") (pin "1") (pinfunction "G_1") (pintype "passive"))
    )
    (net (code "115") (name "unconnected-(Q2-S-Pad3)") (class "Default")
      (node (ref "Q2") (pin "3") (pinfunction "S_3") (pintype "passive"))
    )
    (net (code "116") (name "unconnected-(Q3-D-Pad4)") (class "Default")
      (node (ref "Q3") (pin "4") (pinfunction "D_4") (pintype "passive"))
    )
    (net (code "117") (name "unconnected-(Q3-G-Pad1)") (class "Default")
      (node (ref "Q3") (pin "1") (pinfunction "G_1") (pintype "passive"))
    )
    (net (code "118") (name "unconnected-(Q3-S-Pad3)") (class "Default")
      (node (ref "Q3") (pin "3") (pinfunction "S_3") (pintype "passive"))
    )
    (net (code "119") (name "unconnected-(Q4-D-Pad4)") (class "Default")
      (node (ref "Q4") (pin "4") (pinfunction "D_4") (pintype "passive"))
    )
    (net (code "120") (name "unconnected-(Q4-G-Pad1)") (class "Default")
      (node (ref "Q4") (pin "1") (pinfunction "G_1") (pintype "passive"))
    )
    (net (code "121") (name "unconnected-(Q4-S-Pad3)") (class "Default")
      (node (ref "Q4") (pin "3") (pinfunction "S_3") (pintype "passive"))
    )
    (net (code "122") (name "unconnected-(Q5-D-Pad2)") (class "Default")
      (node (ref "Q5") (pin "2") (pinfunction "D_2") (pintype "passive"))
    )
    (net (code "123") (name "unconnected-(Q5-G-Pad1)") (class "Default")
      (node (ref "Q5") (pin "1") (pinfunction "G_1") (pintype "passive"))
    )
    (net (code "124") (name "unconnected-(Q5-S-Pad3)") (class "Default")
      (node (ref "Q5") (pin "3") (pinfunction "S_3") (pintype "passive"))
    )
    (net (code "125") (name "unconnected-(Q6-D-Pad2)") (class "Default")
      (node (ref "Q6") (pin "2") (pinfunction "D_2") (pintype "passive"))
    )
    (net (code "126") (name "unconnected-(Q6-G-Pad1)") (class "Default")
      (node (ref "Q6") (pin "1") (pinfunction "G_1") (pintype "passive"))
    )
    (net (code "127") (name "unconnected-(Q6-S-Pad3)") (class "Default")
      (node (ref "Q6") (pin "3") (pinfunction "S_3") (pintype "passive"))
    )
  )
)
